# i2c_encoder_6.net
KiCad netlist of a schematic drawn in EAGLE
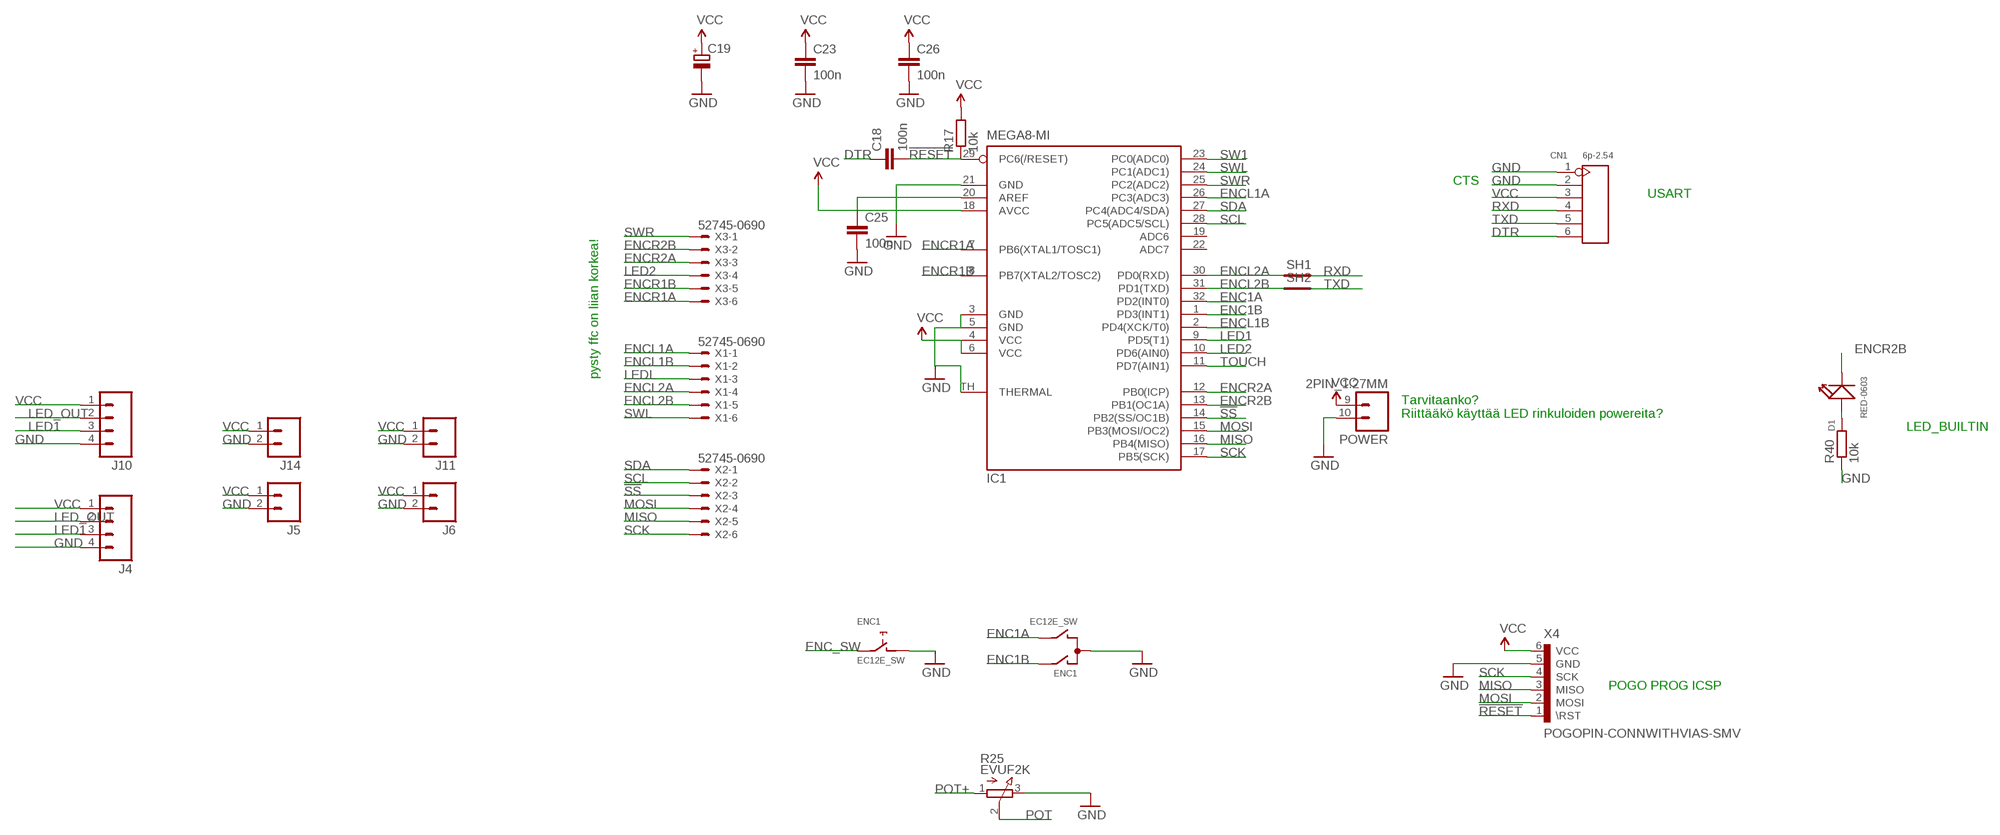
[diagram p0: schematic, sheet 1]
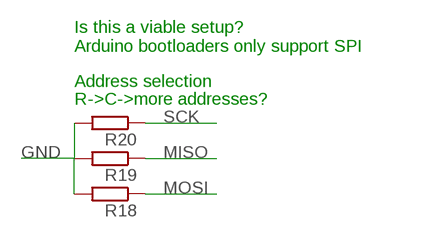
[diagram p1: schematic, sheet 2]
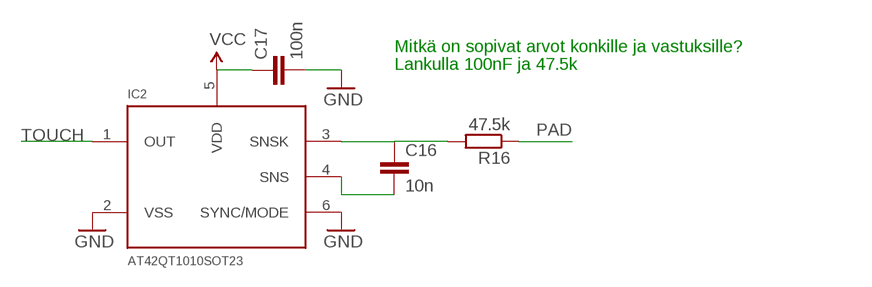
[diagram p2: schematic, sheet 3]
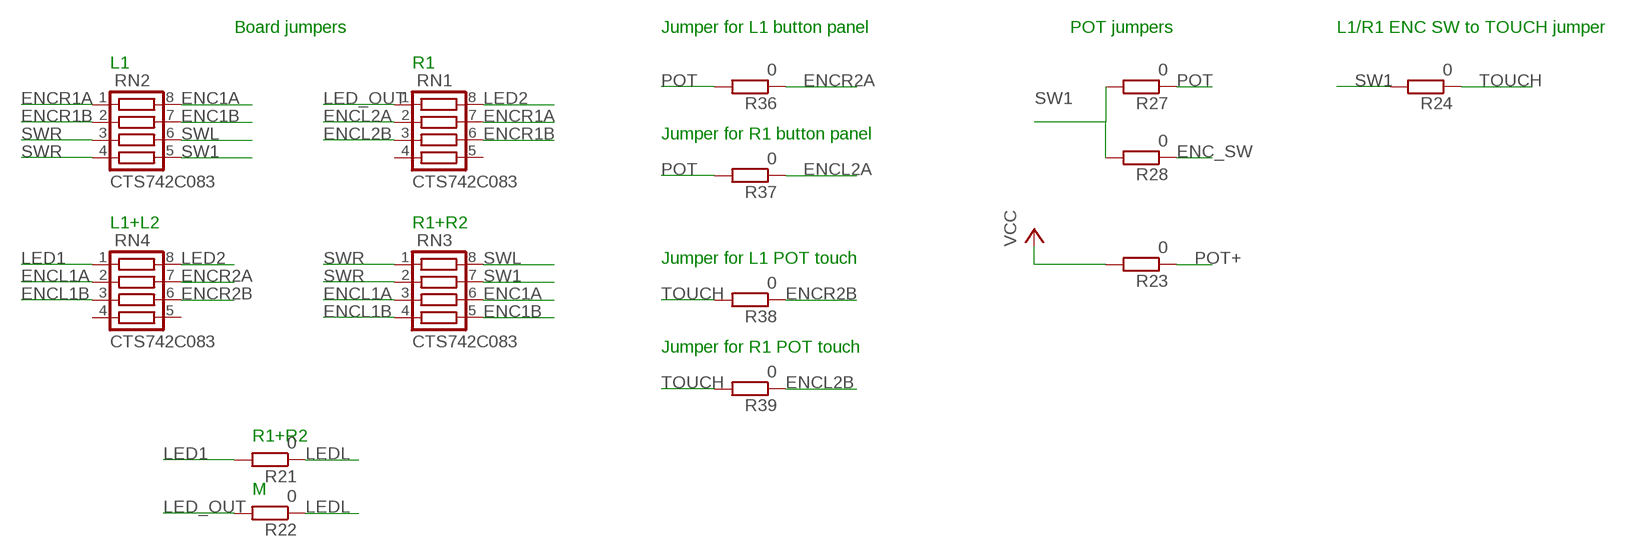
[diagram p3: schematic, sheet 4]
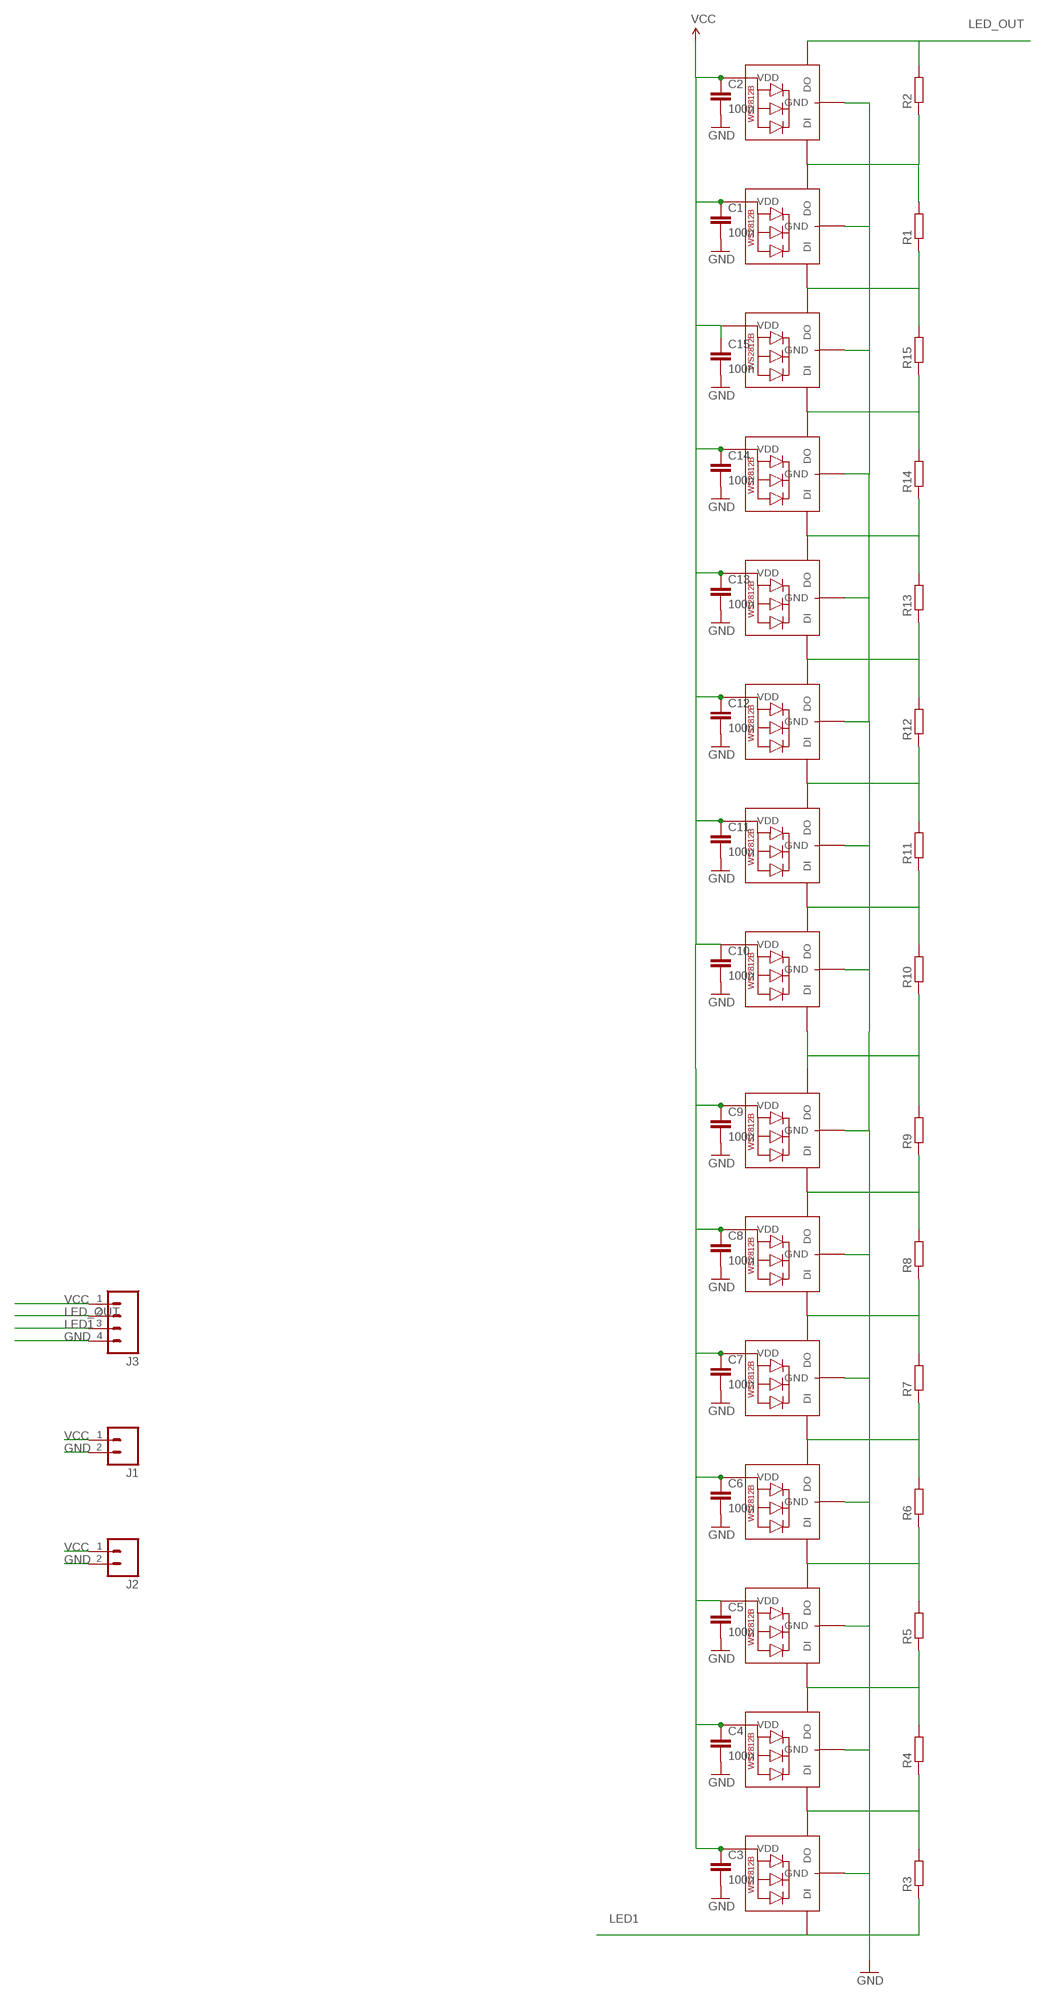
[diagram p4: schematic, sheet 5]
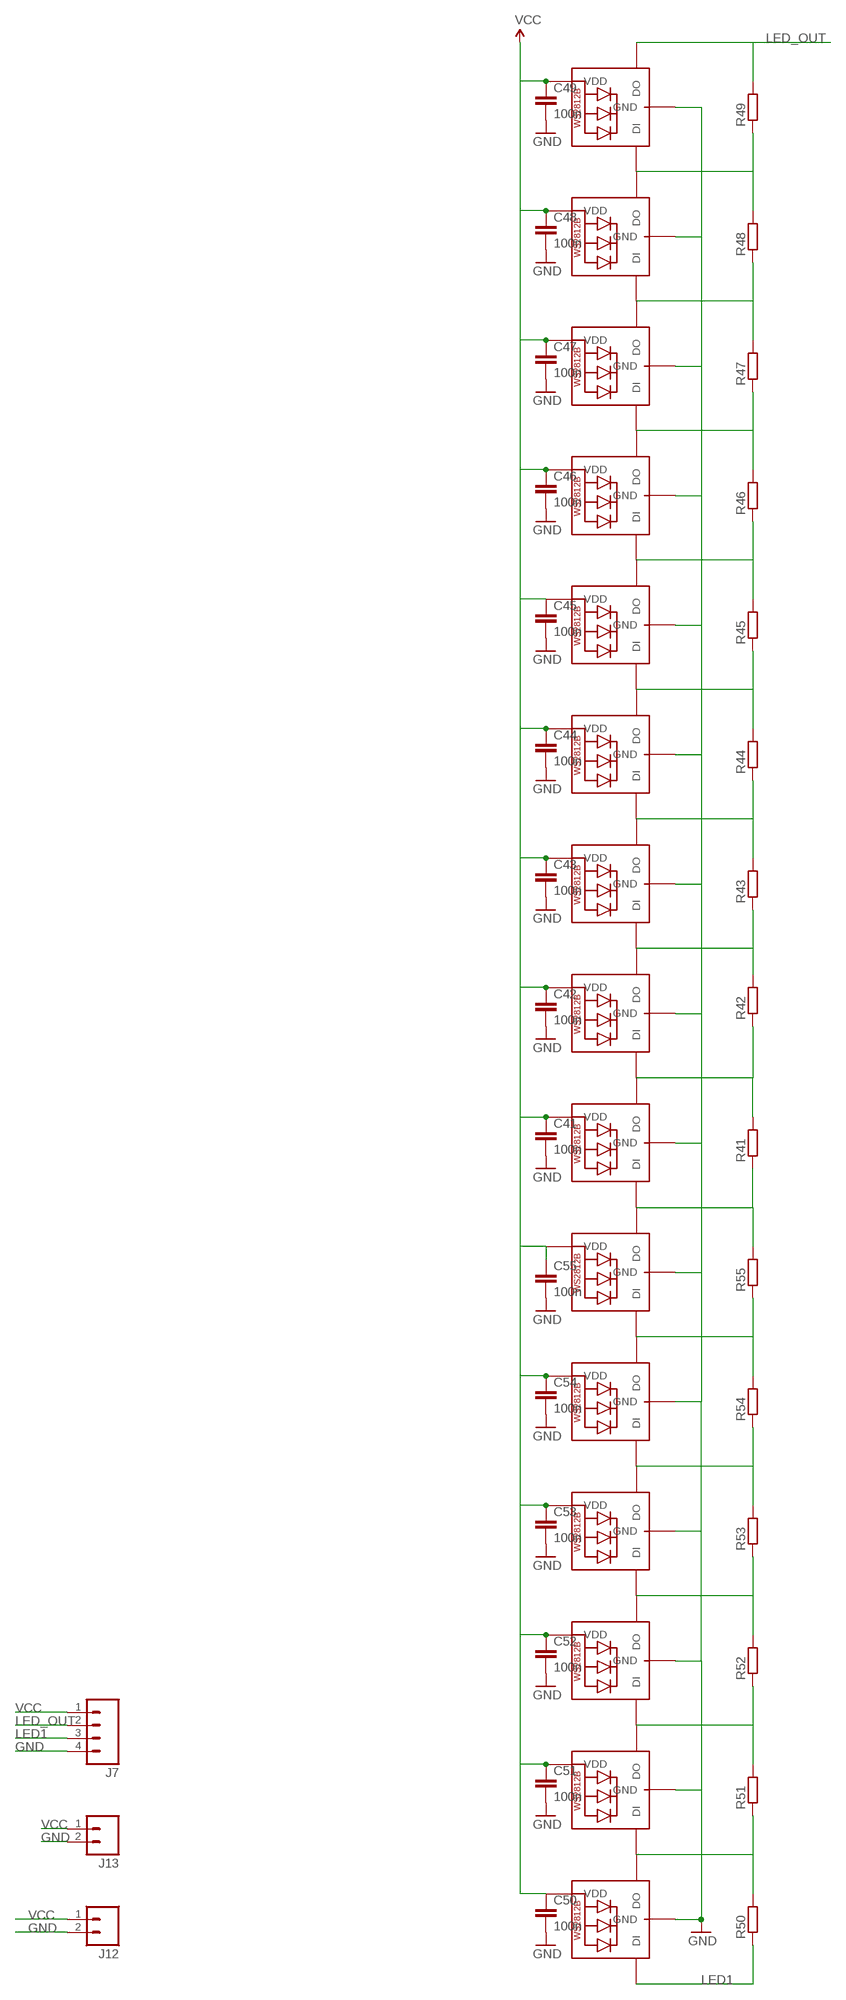
[diagram p5: schematic, sheet 6]
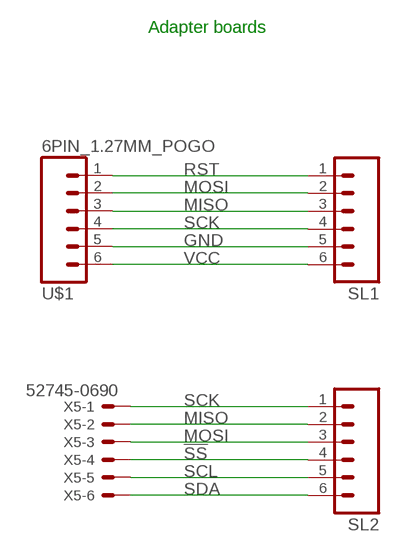
[diagram p6: schematic, sheet 7]
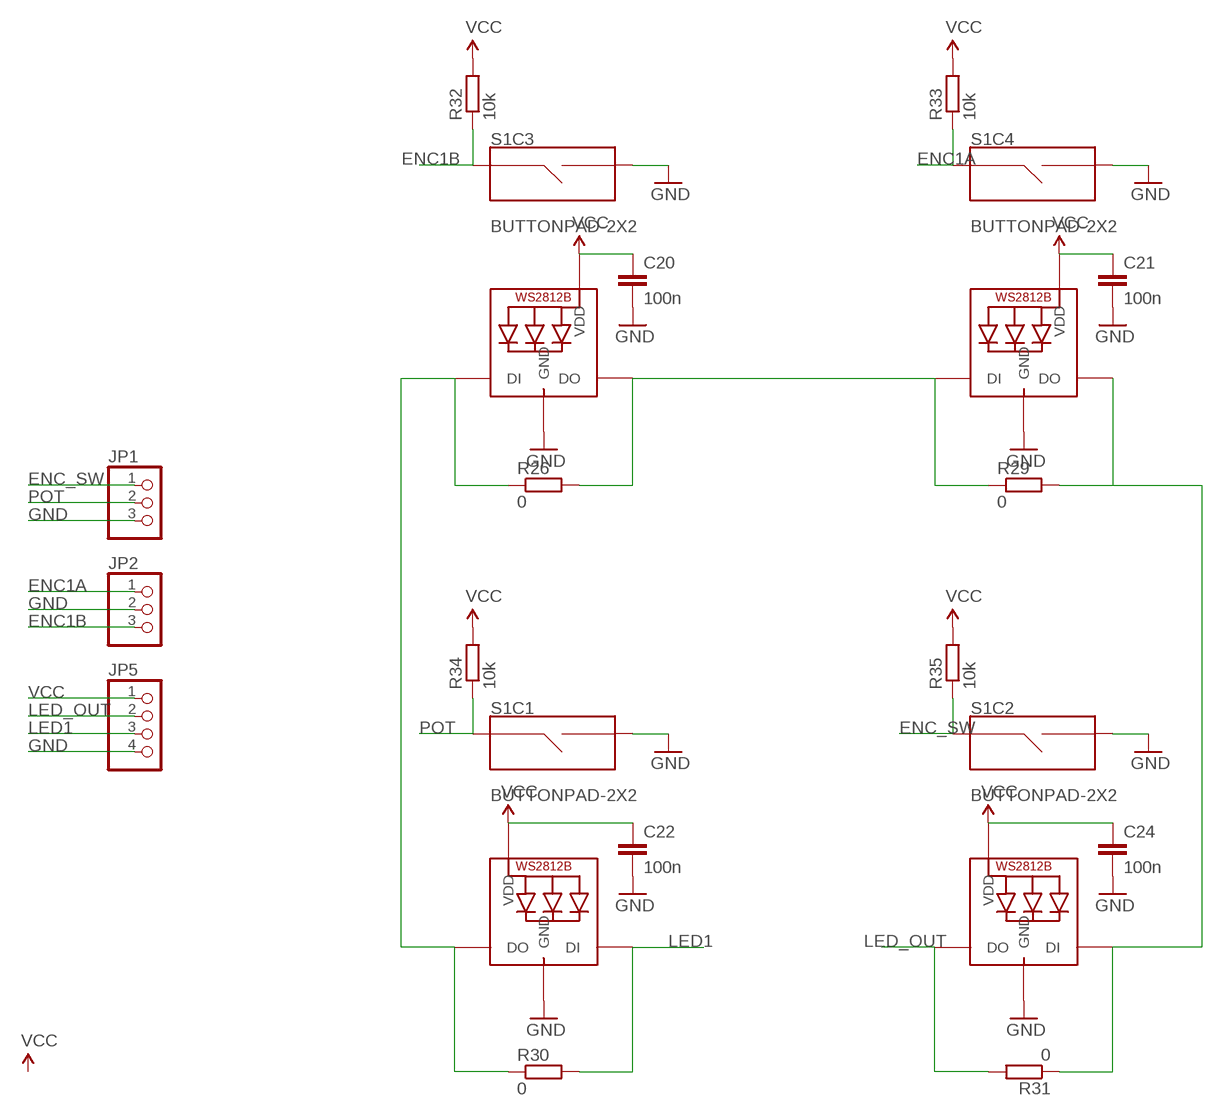
[diagram p7: schematic, sheet 8]

(export (version "E")
  (design (tool "Eeschema 10.0.6"))
  (components
    (comp (ref "C16")
      (value "10n")
      (footprint "eagle-import:0603-CAP")
      (libsource (lib "eagle-import") (part "CAP0603-CAP"))
    )
    (comp (ref "C17")
      (value "100n")
      (footprint "eagle-import:0603-CAP")
      (libsource (lib "eagle-import") (part "CAP0603-CAP"))
    )
    (comp (ref "IC2")
      (value "AT42QT1010SOT23")
      (footprint "eagle-import:SOT23-6")
      (libsource (lib "eagle-import") (part "AT42QT1010SOT23"))
    )
    (comp (ref "R16")
      (value "47.5k")
      (footprint "eagle-import:R0603")
      (libsource (lib "eagle-import") (part "R-EU_R0603"))
    )
    (comp (ref "SL1")
      (value "M06")
      (footprint "eagle-import:06P")
      (libsource (lib "eagle-import") (part "M06"))
    )
    (comp (ref "SL2")
      (value "M06")
      (footprint "eagle-import:06P")
      (libsource (lib "eagle-import") (part "M06"))
    )
    (comp (ref "U$1")
      (value "6PIN_1.27MM_POGO")
      (footprint "eagle-import:1X06-1.27MM_POGO")
      (libsource (lib "eagle-import") (part "6PIN_1.27MM_POGO"))
    )
    (comp (ref "X5")
      (value "52745-0690")
      (footprint "eagle-import:52745-0690")
      (fields (field (name "MF") "MOLEX"))
      (libsource (lib "eagle-import") (part "52745-0690"))
    )
    (comp (ref "R18")
      (value "R-EU_R0603")
      (footprint "eagle-import:R0603")
      (libsource (lib "eagle-import") (part "R-EU_R0603"))
    )
    (comp (ref "R19")
      (value "R-EU_R0603")
      (footprint "eagle-import:R0603")
      (libsource (lib "eagle-import") (part "R-EU_R0603"))
    )
    (comp (ref "R20")
      (value "R-EU_R0603")
      (footprint "eagle-import:R0603")
      (libsource (lib "eagle-import") (part "R-EU_R0603"))
    )
    (comp (ref "R21")
      (value "0")
      (footprint "eagle-import:R0603")
      (libsource (lib "eagle-import") (part "R-EU_R0603"))
    )
    (comp (ref "R22")
      (value "0")
      (footprint "eagle-import:R0603")
      (fields (field (name "SPICEPREFIX") "R"))
      (libsource (lib "eagle-import") (part "R-EU_R0603"))
    )
    (comp (ref "R23")
      (value "0")
      (footprint "eagle-import:R0603")
      (fields (field (name "SPICEPREFIX") "R"))
      (libsource (lib "eagle-import") (part "R-EU_R0603"))
    )
    (comp (ref "R24")
      (value "0")
      (footprint "eagle-import:R0603")
      (fields (field (name "SPICEPREFIX") "R"))
      (libsource (lib "eagle-import") (part "R-EU_R0603"))
    )
    (comp (ref "R27")
      (value "0")
      (footprint "eagle-import:R0603")
      (fields (field (name "SPICEPREFIX") "R"))
      (libsource (lib "eagle-import") (part "R-EU_R0603"))
    )
    (comp (ref "R28")
      (value "0")
      (footprint "eagle-import:R0603")
      (fields (field (name "SPICEPREFIX") "R"))
      (libsource (lib "eagle-import") (part "R-EU_R0603"))
    )
    (comp (ref "R36")
      (value "0")
      (footprint "eagle-import:R0603")
      (fields (field (name "SPICEPREFIX") "R"))
      (libsource (lib "eagle-import") (part "R-EU_R0603"))
    )
    (comp (ref "R37")
      (value "0")
      (footprint "eagle-import:R0603")
      (fields (field (name "SPICEPREFIX") "R"))
      (libsource (lib "eagle-import") (part "R-EU_R0603"))
    )
    (comp (ref "R38")
      (value "0")
      (footprint "eagle-import:R0603")
      (fields (field (name "SPICEPREFIX") "R"))
      (libsource (lib "eagle-import") (part "R-EU_R0603"))
    )
    (comp (ref "R39")
      (value "0")
      (footprint "eagle-import:R0603")
      (fields (field (name "SPICEPREFIX") "R"))
      (libsource (lib "eagle-import") (part "R-EU_R0603"))
    )
    (comp (ref "RN1")
      (value "CTS742C083")
      (footprint "eagle-import:CTS742C083")
      (libsource (lib "eagle-import") (part "CTS742C083"))
    )
    (comp (ref "RN2")
      (value "CTS742C083")
      (footprint "eagle-import:CTS742C083")
      (libsource (lib "eagle-import") (part "CTS742C083"))
    )
    (comp (ref "RN3")
      (value "CTS742C083")
      (footprint "eagle-import:CTS742C083")
      (libsource (lib "eagle-import") (part "CTS742C083"))
    )
    (comp (ref "RN4")
      (value "CTS742C083")
      (footprint "eagle-import:CTS742C083")
      (libsource (lib "eagle-import") (part "CTS742C083"))
    )
    (comp (ref "C18")
      (value "100n")
      (footprint "eagle-import:0603-CAP")
      (libsource (lib "eagle-import") (part "CAP0603-CAP"))
    )
    (comp (ref "C19")
      (value "CPOL-EUC")
      (footprint "eagle-import:PANASONIC_C")
      (libsource (lib "eagle-import") (part "CPOL-EUC"))
    )
    (comp (ref "C23")
      (value "100n")
      (footprint "eagle-import:0603-CAP")
      (libsource (lib "eagle-import") (part "CAP0603-CAP"))
    )
    (comp (ref "C25")
      (value "100n")
      (footprint "eagle-import:0603-CAP")
      (libsource (lib "eagle-import") (part "CAP0603-CAP"))
    )
    (comp (ref "C26")
      (value "100n")
      (footprint "eagle-import:0603-CAP")
      (libsource (lib "eagle-import") (part "CAP0603-CAP"))
    )
    (comp (ref "CN1")
      (value "6p-2.54")
      (footprint "eagle-import:H6-2.54")
      (fields (field (name "MPN") "F185-1106A1BSYC1"))
      (libsource (lib "eagle-import") (part "DIP-BLACK-FEMALE-HEADER-VERT(6P-2.54)"))
    )
    (comp (ref "D1")
      (value "RED-0603")
      (footprint "eagle-import:LED-0603")
      (fields (field (name "MPN") "19-217-R6C-AL1M2VY-3T"))
      (libsource (lib "eagle-import") (part "LED-SMD-RED-DIFFUSED(0603)"))
    )
    (comp (ref "ENC1")
      (value "EC12E_SW")
      (footprint "eagle-import:ALPS_EC12E_SW")
      (fields (field (name "MPN") "EC12E2424407"))
      (libsource (lib "eagle-import") (part "EC12E_SW"))
    )
    (comp (ref "IC1")
      (value "MEGA8-MI")
      (footprint "eagle-import:MLF32-TH")
      (fields (field (name "MPN") "ATMEGA88PA-MU"))
      (libsource (lib "eagle-import") (part "MEGA8-MI"))
    )
    (comp (ref "J4")
      (value "M04NO_SILK_ALL_ROUND")
      (footprint "eagle-import:1X04_NO_SILK_ALL_ROUND")
      (libsource (lib "eagle-import") (part "M04NO_SILK_ALL_ROUND"))
    )
    (comp (ref "J5")
      (value "M021X02_NO_SILK")
      (footprint "eagle-import:1X02_NO_SILK")
      (libsource (lib "eagle-import") (part "M021X02_NO_SILK"))
    )
    (comp (ref "J6")
      (value "M021X02_NO_SILK")
      (footprint "eagle-import:1X02_NO_SILK")
      (libsource (lib "eagle-import") (part "M021X02_NO_SILK"))
    )
    (comp (ref "J10")
      (value "M04NO_SILK_ALL_ROUND")
      (footprint "eagle-import:1X04_NO_SILK_ALL_ROUND")
      (libsource (lib "eagle-import") (part "M04NO_SILK_ALL_ROUND"))
    )
    (comp (ref "J11")
      (value "M021X02_NO_SILK")
      (footprint "eagle-import:1X02_NO_SILK")
      (libsource (lib "eagle-import") (part "M021X02_NO_SILK"))
    )
    (comp (ref "J14")
      (value "M021X02_NO_SILK")
      (footprint "eagle-import:1X02_NO_SILK")
      (libsource (lib "eagle-import") (part "M021X02_NO_SILK"))
    )
    (comp (ref "POWER")
      (value "2PIN_1.27MM")
      (footprint "eagle-import:1X02_1.27MM_NO_SILK")
      (libsource (lib "eagle-import") (part "2PIN_1.27MM"))
    )
    (comp (ref "R17")
      (value "10k")
      (footprint "eagle-import:R0603")
      (libsource (lib "eagle-import") (part "R-EU_R0603"))
    )
    (comp (ref "R25")
      (value "EVUF2K")
      (footprint "eagle-import:EVUFXK")
      (libsource (lib "eagle-import") (part "EVUF2K"))
    )
    (comp (ref "R40")
      (value "10k")
      (footprint "eagle-import:R0603")
      (libsource (lib "eagle-import") (part "R-EU_R0603"))
    )
    (comp (ref "SH1")
      (value "SHORT")
      (footprint "eagle-import:SHORT_TOP_8MIL")
      (libsource (lib "eagle-import") (part "SHORT"))
    )
    (comp (ref "SH2")
      (value "SHORT")
      (footprint "eagle-import:SHORT_TOP_8MIL")
      (libsource (lib "eagle-import") (part "SHORT"))
    )
    (comp (ref "X1")
      (value "52745-0690")
      (footprint "eagle-import:52745-0690")
      (fields (field (name "MF") "MOLEX"))
      (libsource (lib "eagle-import") (part "52745-0690"))
    )
    (comp (ref "X2")
      (value "52745-0690")
      (footprint "eagle-import:52745-0690")
      (fields (field (name "MF") "MOLEX"))
      (libsource (lib "eagle-import") (part "52745-0690"))
    )
    (comp (ref "X3")
      (value "52745-0690")
      (footprint "eagle-import:52745-0690")
      (fields (field (name "MF") "MOLEX"))
      (libsource (lib "eagle-import") (part "52745-0690"))
    )
    (comp (ref "X4")
      (value "POGOPIN-CONNWITHVIAS-SMV")
      (footprint "eagle-import:POGOPROG-CONN-OH-SMALLERVIAS")
      (libsource (lib "eagle-import") (part "POGOPIN-CONNWITHVIAS-SMV"))
    )
    (comp (ref "C20")
      (value "100n")
      (footprint "eagle-import:0603-CAP")
      (libsource (lib "eagle-import") (part "CAP0603-CAP"))
    )
    (comp (ref "C21")
      (value "100n")
      (footprint "eagle-import:0603-CAP")
      (libsource (lib "eagle-import") (part "CAP0603-CAP"))
    )
    (comp (ref "C22")
      (value "100n")
      (footprint "eagle-import:0603-CAP")
      (libsource (lib "eagle-import") (part "CAP0603-CAP"))
    )
    (comp (ref "C24")
      (value "100n")
      (footprint "eagle-import:0603-CAP")
      (libsource (lib "eagle-import") (part "CAP0603-CAP"))
    )
    (comp (ref "JP1")
      (value "PINHD-1X31X03_SMT")
      (footprint "eagle-import:1X03_SMT")
      (libsource (lib "eagle-import") (part "PINHD-1X31X03_SMT"))
    )
    (comp (ref "JP2")
      (value "PINHD-1X31X03_SMT")
      (footprint "eagle-import:1X03_SMT")
      (libsource (lib "eagle-import") (part "PINHD-1X31X03_SMT"))
    )
    (comp (ref "JP5")
      (value "PINHD-1X41X04_SMT")
      (footprint "eagle-import:1X04_SMT")
      (libsource (lib "eagle-import") (part "PINHD-1X41X04_SMT"))
    )
    (comp (ref "LED16")
      (value "WS2812B3535")
      (footprint "eagle-import:LED3535")
      (libsource (lib "eagle-import") (part "WS2812B3535"))
    )
    (comp (ref "LED17")
      (value "WS2812B3535")
      (footprint "eagle-import:LED3535")
      (libsource (lib "eagle-import") (part "WS2812B3535"))
    )
    (comp (ref "LED18")
      (value "WS2812B3535")
      (footprint "eagle-import:LED3535")
      (libsource (lib "eagle-import") (part "WS2812B3535"))
    )
    (comp (ref "LED19")
      (value "WS2812B3535")
      (footprint "eagle-import:LED3535")
      (libsource (lib "eagle-import") (part "WS2812B3535"))
    )
    (comp (ref "R26")
      (value "0")
      (footprint "eagle-import:R0603")
      (libsource (lib "eagle-import") (part "R-EU_R0603"))
    )
    (comp (ref "R29")
      (value "0")
      (footprint "eagle-import:R0603")
      (libsource (lib "eagle-import") (part "R-EU_R0603"))
    )
    (comp (ref "R30")
      (value "0")
      (footprint "eagle-import:R0603")
      (libsource (lib "eagle-import") (part "R-EU_R0603"))
    )
    (comp (ref "R31")
      (value "0")
      (footprint "eagle-import:R0603")
      (libsource (lib "eagle-import") (part "R-EU_R0603"))
    )
    (comp (ref "R32")
      (value "10k")
      (footprint "eagle-import:R0603")
      (libsource (lib "eagle-import") (part "R-EU_R0603"))
    )
    (comp (ref "R33")
      (value "10k")
      (footprint "eagle-import:R0603")
      (libsource (lib "eagle-import") (part "R-EU_R0603"))
    )
    (comp (ref "R34")
      (value "10k")
      (footprint "eagle-import:R0603")
      (libsource (lib "eagle-import") (part "R-EU_R0603"))
    )
    (comp (ref "R35")
      (value "10k")
      (footprint "eagle-import:R0603")
      (libsource (lib "eagle-import") (part "R-EU_R0603"))
    )
    (comp (ref "S1")
      (value "BUTTONPAD-2X2")
      (footprint "eagle-import:BUTTONPAD-2X2-SINGLE")
      (libsource (lib "eagle-import") (part "BUTTONPAD-2X2"))
    )
    (comp (ref "C1")
      (value "100n")
      (footprint "eagle-import:0603-CAP")
      (libsource (lib "eagle-import") (part "CAP0603-CAP"))
    )
    (comp (ref "C2")
      (value "100n")
      (footprint "eagle-import:0603-CAP")
      (libsource (lib "eagle-import") (part "CAP0603-CAP"))
    )
    (comp (ref "C3")
      (value "100n")
      (footprint "eagle-import:0603-CAP")
      (libsource (lib "eagle-import") (part "CAP0603-CAP"))
    )
    (comp (ref "C4")
      (value "100n")
      (footprint "eagle-import:0603-CAP")
      (libsource (lib "eagle-import") (part "CAP0603-CAP"))
    )
    (comp (ref "C5")
      (value "100n")
      (footprint "eagle-import:0603-CAP")
      (libsource (lib "eagle-import") (part "CAP0603-CAP"))
    )
    (comp (ref "C6")
      (value "100n")
      (footprint "eagle-import:0603-CAP")
      (libsource (lib "eagle-import") (part "CAP0603-CAP"))
    )
    (comp (ref "C7")
      (value "100n")
      (footprint "eagle-import:0603-CAP")
      (libsource (lib "eagle-import") (part "CAP0603-CAP"))
    )
    (comp (ref "C8")
      (value "100n")
      (footprint "eagle-import:0603-CAP")
      (libsource (lib "eagle-import") (part "CAP0603-CAP"))
    )
    (comp (ref "C9")
      (value "100n")
      (footprint "eagle-import:0603-CAP")
      (libsource (lib "eagle-import") (part "CAP0603-CAP"))
    )
    (comp (ref "C10")
      (value "100n")
      (footprint "eagle-import:0603-CAP")
      (libsource (lib "eagle-import") (part "CAP0603-CAP"))
    )
    (comp (ref "C11")
      (value "100n")
      (footprint "eagle-import:0603-CAP")
      (libsource (lib "eagle-import") (part "CAP0603-CAP"))
    )
    (comp (ref "C12")
      (value "100n")
      (footprint "eagle-import:0603-CAP")
      (libsource (lib "eagle-import") (part "CAP0603-CAP"))
    )
    (comp (ref "C13")
      (value "100n")
      (footprint "eagle-import:0603-CAP")
      (libsource (lib "eagle-import") (part "CAP0603-CAP"))
    )
    (comp (ref "C14")
      (value "100n")
      (footprint "eagle-import:0603-CAP")
      (libsource (lib "eagle-import") (part "CAP0603-CAP"))
    )
    (comp (ref "C15")
      (value "100n")
      (footprint "eagle-import:0603-CAP")
      (libsource (lib "eagle-import") (part "CAP0603-CAP"))
    )
    (comp (ref "J1")
      (value "M021X02_NO_SILK")
      (footprint "eagle-import:1X02_NO_SILK")
      (libsource (lib "eagle-import") (part "M021X02_NO_SILK"))
    )
    (comp (ref "J2")
      (value "M021X02_NO_SILK")
      (footprint "eagle-import:1X02_NO_SILK")
      (libsource (lib "eagle-import") (part "M021X02_NO_SILK"))
    )
    (comp (ref "J3")
      (value "M04NO_SILK_ALL_ROUND")
      (footprint "eagle-import:1X04_NO_SILK_ALL_ROUND")
      (libsource (lib "eagle-import") (part "M04NO_SILK_ALL_ROUND"))
    )
    (comp (ref "LED1")
      (value "WS2812B3535")
      (footprint "eagle-import:LED3535")
      (libsource (lib "eagle-import") (part "WS2812B3535"))
    )
    (comp (ref "LED2")
      (value "WS2812B3535")
      (footprint "eagle-import:LED3535")
      (libsource (lib "eagle-import") (part "WS2812B3535"))
    )
    (comp (ref "LED3")
      (value "WS2812B3535")
      (footprint "eagle-import:LED3535")
      (libsource (lib "eagle-import") (part "WS2812B3535"))
    )
    (comp (ref "LED4")
      (value "WS2812B3535")
      (footprint "eagle-import:LED3535")
      (fields (field (name "SPICEPREFIX") "E"))
      (libsource (lib "eagle-import") (part "WS2812B3535"))
    )
    (comp (ref "LED5")
      (value "WS2812B3535")
      (footprint "eagle-import:LED3535")
      (libsource (lib "eagle-import") (part "WS2812B3535"))
    )
    (comp (ref "LED6")
      (value "WS2812B3535")
      (footprint "eagle-import:LED3535")
      (libsource (lib "eagle-import") (part "WS2812B3535"))
    )
    (comp (ref "LED7")
      (value "WS2812B3535")
      (footprint "eagle-import:LED3535")
      (libsource (lib "eagle-import") (part "WS2812B3535"))
    )
    (comp (ref "LED8")
      (value "WS2812B3535")
      (footprint "eagle-import:LED3535")
      (libsource (lib "eagle-import") (part "WS2812B3535"))
    )
    (comp (ref "LED9")
      (value "WS2812B3535")
      (footprint "eagle-import:LED3535")
      (libsource (lib "eagle-import") (part "WS2812B3535"))
    )
    (comp (ref "LED10")
      (value "WS2812B3535")
      (footprint "eagle-import:LED3535")
      (libsource (lib "eagle-import") (part "WS2812B3535"))
    )
    (comp (ref "LED11")
      (value "WS2812B3535")
      (footprint "eagle-import:LED3535")
      (libsource (lib "eagle-import") (part "WS2812B3535"))
    )
    (comp (ref "LED12")
      (value "WS2812B3535")
      (footprint "eagle-import:LED3535")
      (libsource (lib "eagle-import") (part "WS2812B3535"))
    )
    (comp (ref "LED13")
      (value "WS2812B3535")
      (footprint "eagle-import:LED3535")
      (libsource (lib "eagle-import") (part "WS2812B3535"))
    )
    (comp (ref "LED14")
      (value "WS2812B3535")
      (footprint "eagle-import:LED3535")
      (libsource (lib "eagle-import") (part "WS2812B3535"))
    )
    (comp (ref "LED15")
      (value "WS2812B3535")
      (footprint "eagle-import:LED3535")
      (libsource (lib "eagle-import") (part "WS2812B3535"))
    )
    (comp (ref "R1")
      (value "R-EU_R0603")
      (footprint "eagle-import:R0603")
      (libsource (lib "eagle-import") (part "R-EU_R0603"))
    )
    (comp (ref "R2")
      (value "R-EU_R0603")
      (footprint "eagle-import:R0603")
      (libsource (lib "eagle-import") (part "R-EU_R0603"))
    )
    (comp (ref "R3")
      (value "R-EU_R0603")
      (footprint "eagle-import:R0603")
      (libsource (lib "eagle-import") (part "R-EU_R0603"))
    )
    (comp (ref "R4")
      (value "R-EU_R0603")
      (footprint "eagle-import:R0603")
      (libsource (lib "eagle-import") (part "R-EU_R0603"))
    )
    (comp (ref "R5")
      (value "R-EU_R0603")
      (footprint "eagle-import:R0603")
      (libsource (lib "eagle-import") (part "R-EU_R0603"))
    )
    (comp (ref "R6")
      (value "R-EU_R0603")
      (footprint "eagle-import:R0603")
      (libsource (lib "eagle-import") (part "R-EU_R0603"))
    )
    (comp (ref "R7")
      (value "R-EU_R0603")
      (footprint "eagle-import:R0603")
      (libsource (lib "eagle-import") (part "R-EU_R0603"))
    )
    (comp (ref "R8")
      (value "R-EU_R0603")
      (footprint "eagle-import:R0603")
      (libsource (lib "eagle-import") (part "R-EU_R0603"))
    )
    (comp (ref "R9")
      (value "R-EU_R0603")
      (footprint "eagle-import:R0603")
      (libsource (lib "eagle-import") (part "R-EU_R0603"))
    )
    (comp (ref "R10")
      (value "R-EU_R0603")
      (footprint "eagle-import:R0603")
      (libsource (lib "eagle-import") (part "R-EU_R0603"))
    )
    (comp (ref "R11")
      (value "R-EU_R0603")
      (footprint "eagle-import:R0603")
      (libsource (lib "eagle-import") (part "R-EU_R0603"))
    )
    (comp (ref "R12")
      (value "R-EU_R0603")
      (footprint "eagle-import:R0603")
      (libsource (lib "eagle-import") (part "R-EU_R0603"))
    )
    (comp (ref "R13")
      (value "R-EU_R0603")
      (footprint "eagle-import:R0603")
      (libsource (lib "eagle-import") (part "R-EU_R0603"))
    )
    (comp (ref "R14")
      (value "R-EU_R0603")
      (footprint "eagle-import:R0603")
      (libsource (lib "eagle-import") (part "R-EU_R0603"))
    )
    (comp (ref "R15")
      (value "R-EU_R0603")
      (footprint "eagle-import:R0603")
      (libsource (lib "eagle-import") (part "R-EU_R0603"))
    )
    (comp (ref "C41")
      (value "100n")
      (footprint "eagle-import:0603-CAP")
      (libsource (lib "eagle-import") (part "CAP0603-CAP"))
    )
    (comp (ref "C42")
      (value "100n")
      (footprint "eagle-import:0603-CAP")
      (libsource (lib "eagle-import") (part "CAP0603-CAP"))
    )
    (comp (ref "C43")
      (value "100n")
      (footprint "eagle-import:0603-CAP")
      (libsource (lib "eagle-import") (part "CAP0603-CAP"))
    )
    (comp (ref "C44")
      (value "100n")
      (footprint "eagle-import:0603-CAP")
      (libsource (lib "eagle-import") (part "CAP0603-CAP"))
    )
    (comp (ref "C45")
      (value "100n")
      (footprint "eagle-import:0603-CAP")
      (libsource (lib "eagle-import") (part "CAP0603-CAP"))
    )
    (comp (ref "C46")
      (value "100n")
      (footprint "eagle-import:0603-CAP")
      (libsource (lib "eagle-import") (part "CAP0603-CAP"))
    )
    (comp (ref "C47")
      (value "100n")
      (footprint "eagle-import:0603-CAP")
      (libsource (lib "eagle-import") (part "CAP0603-CAP"))
    )
    (comp (ref "C48")
      (value "100n")
      (footprint "eagle-import:0603-CAP")
      (libsource (lib "eagle-import") (part "CAP0603-CAP"))
    )
    (comp (ref "C49")
      (value "100n")
      (footprint "eagle-import:0603-CAP")
      (libsource (lib "eagle-import") (part "CAP0603-CAP"))
    )
    (comp (ref "C50")
      (value "100n")
      (footprint "eagle-import:0603-CAP")
      (libsource (lib "eagle-import") (part "CAP0603-CAP"))
    )
    (comp (ref "C51")
      (value "100n")
      (footprint "eagle-import:0603-CAP")
      (libsource (lib "eagle-import") (part "CAP0603-CAP"))
    )
    (comp (ref "C52")
      (value "100n")
      (footprint "eagle-import:0603-CAP")
      (libsource (lib "eagle-import") (part "CAP0603-CAP"))
    )
    (comp (ref "C53")
      (value "100n")
      (footprint "eagle-import:0603-CAP")
      (libsource (lib "eagle-import") (part "CAP0603-CAP"))
    )
    (comp (ref "C54")
      (value "100n")
      (footprint "eagle-import:0603-CAP")
      (libsource (lib "eagle-import") (part "CAP0603-CAP"))
    )
    (comp (ref "C55")
      (value "100n")
      (footprint "eagle-import:0603-CAP")
      (libsource (lib "eagle-import") (part "CAP0603-CAP"))
    )
    (comp (ref "J7")
      (value "M04NO_SILK_ALL_ROUND")
      (footprint "eagle-import:1X04_NO_SILK_ALL_ROUND")
      (libsource (lib "eagle-import") (part "M04NO_SILK_ALL_ROUND"))
    )
    (comp (ref "J12")
      (value "M021X02_NO_SILK")
      (footprint "eagle-import:1X02_NO_SILK")
      (libsource (lib "eagle-import") (part "M021X02_NO_SILK"))
    )
    (comp (ref "J13")
      (value "M021X02_NO_SILK")
      (footprint "eagle-import:1X02_NO_SILK")
      (libsource (lib "eagle-import") (part "M021X02_NO_SILK"))
    )
    (comp (ref "LED31")
      (value "WS2812B3535")
      (footprint "eagle-import:LED3535")
      (libsource (lib "eagle-import") (part "WS2812B3535"))
    )
    (comp (ref "LED32")
      (value "WS2812B3535")
      (footprint "eagle-import:LED3535")
      (libsource (lib "eagle-import") (part "WS2812B3535"))
    )
    (comp (ref "LED33")
      (value "WS2812B3535")
      (footprint "eagle-import:LED3535")
      (libsource (lib "eagle-import") (part "WS2812B3535"))
    )
    (comp (ref "LED34")
      (value "WS2812B3535")
      (footprint "eagle-import:LED3535")
      (libsource (lib "eagle-import") (part "WS2812B3535"))
    )
    (comp (ref "LED35")
      (value "WS2812B3535")
      (footprint "eagle-import:LED3535")
      (libsource (lib "eagle-import") (part "WS2812B3535"))
    )
    (comp (ref "LED36")
      (value "WS2812B3535")
      (footprint "eagle-import:LED3535")
      (libsource (lib "eagle-import") (part "WS2812B3535"))
    )
    (comp (ref "LED37")
      (value "WS2812B3535")
      (footprint "eagle-import:LED3535")
      (libsource (lib "eagle-import") (part "WS2812B3535"))
    )
    (comp (ref "LED38")
      (value "WS2812B3535")
      (footprint "eagle-import:LED3535")
      (libsource (lib "eagle-import") (part "WS2812B3535"))
    )
    (comp (ref "LED39")
      (value "WS2812B3535")
      (footprint "eagle-import:LED3535")
      (libsource (lib "eagle-import") (part "WS2812B3535"))
    )
    (comp (ref "LED40")
      (value "WS2812B3535")
      (footprint "eagle-import:LED3535")
      (libsource (lib "eagle-import") (part "WS2812B3535"))
    )
    (comp (ref "LED41")
      (value "WS2812B3535")
      (footprint "eagle-import:LED3535")
      (libsource (lib "eagle-import") (part "WS2812B3535"))
    )
    (comp (ref "LED42")
      (value "WS2812B3535")
      (footprint "eagle-import:LED3535")
      (libsource (lib "eagle-import") (part "WS2812B3535"))
    )
    (comp (ref "LED43")
      (value "WS2812B3535")
      (footprint "eagle-import:LED3535")
      (libsource (lib "eagle-import") (part "WS2812B3535"))
    )
    (comp (ref "LED44")
      (value "WS2812B3535")
      (footprint "eagle-import:LED3535")
      (libsource (lib "eagle-import") (part "WS2812B3535"))
    )
    (comp (ref "LED45")
      (value "WS2812B3535")
      (footprint "eagle-import:LED3535")
      (libsource (lib "eagle-import") (part "WS2812B3535"))
    )
    (comp (ref "R41")
      (value "R-EU_R0603")
      (footprint "eagle-import:R0603")
      (libsource (lib "eagle-import") (part "R-EU_R0603"))
    )
    (comp (ref "R42")
      (value "R-EU_R0603")
      (footprint "eagle-import:R0603")
      (libsource (lib "eagle-import") (part "R-EU_R0603"))
    )
    (comp (ref "R43")
      (value "R-EU_R0603")
      (footprint "eagle-import:R0603")
      (libsource (lib "eagle-import") (part "R-EU_R0603"))
    )
    (comp (ref "R44")
      (value "R-EU_R0603")
      (footprint "eagle-import:R0603")
      (libsource (lib "eagle-import") (part "R-EU_R0603"))
    )
    (comp (ref "R45")
      (value "R-EU_R0603")
      (footprint "eagle-import:R0603")
      (libsource (lib "eagle-import") (part "R-EU_R0603"))
    )
    (comp (ref "R46")
      (value "R-EU_R0603")
      (footprint "eagle-import:R0603")
      (libsource (lib "eagle-import") (part "R-EU_R0603"))
    )
    (comp (ref "R47")
      (value "R-EU_R0603")
      (footprint "eagle-import:R0603")
      (libsource (lib "eagle-import") (part "R-EU_R0603"))
    )
    (comp (ref "R48")
      (value "R-EU_R0603")
      (footprint "eagle-import:R0603")
      (libsource (lib "eagle-import") (part "R-EU_R0603"))
    )
    (comp (ref "R49")
      (value "R-EU_R0603")
      (footprint "eagle-import:R0603")
      (libsource (lib "eagle-import") (part "R-EU_R0603"))
    )
    (comp (ref "R50")
      (value "R-EU_R0603")
      (footprint "eagle-import:R0603")
      (libsource (lib "eagle-import") (part "R-EU_R0603"))
    )
    (comp (ref "R51")
      (value "R-EU_R0603")
      (footprint "eagle-import:R0603")
      (libsource (lib "eagle-import") (part "R-EU_R0603"))
    )
    (comp (ref "R52")
      (value "R-EU_R0603")
      (footprint "eagle-import:R0603")
      (libsource (lib "eagle-import") (part "R-EU_R0603"))
    )
    (comp (ref "R53")
      (value "R-EU_R0603")
      (footprint "eagle-import:R0603")
      (libsource (lib "eagle-import") (part "R-EU_R0603"))
    )
    (comp (ref "R54")
      (value "R-EU_R0603")
      (footprint "eagle-import:R0603")
      (libsource (lib "eagle-import") (part "R-EU_R0603"))
    )
    (comp (ref "R55")
      (value "R-EU_R0603")
      (footprint "eagle-import:R0603")
      (libsource (lib "eagle-import") (part "R-EU_R0603"))
    )
  )
  (nets
    (net (code "1") (name "DTR") (class "Default")
      (node (ref "C18") (pin "1") (pinfunction "1_1") (pintype "passive"))
      (node (ref "CN1") (pin "6") (pinfunction "6_6") (pintype "bidirectional"))
    )
    (net (code "2") (name "ENC1A") (class "Default")
      (node (ref "ENC1") (pin "B") (pinfunction "B_B") (pintype "passive"))
      (node (ref "IC1") (pin "32") (pinfunction "PD2(INT0)_32") (pintype "bidirectional"))
      (node (ref "JP2") (pin "1") (pinfunction "1_1") (pintype "passive"))
      (node (ref "R33") (pin "1") (pinfunction "1_1") (pintype "passive"))
      (node (ref "RN2") (pin "8") (pinfunction "8_8") (pintype "passive"))
      (node (ref "RN3") (pin "6") (pinfunction "6_6") (pintype "passive"))
      (node (ref "S1") (pin "SIG7") (pinfunction "SIG1_SIG7") (pintype "bidirectional"))
    )
    (net (code "3") (name "ENC1B") (class "Default")
      (node (ref "ENC1") (pin "A") (pinfunction "A_A") (pintype "passive"))
      (node (ref "IC1") (pin "1") (pinfunction "PD3(INT1)_1") (pintype "bidirectional"))
      (node (ref "JP2") (pin "3") (pinfunction "3_3") (pintype "passive"))
      (node (ref "R32") (pin "1") (pinfunction "1_1") (pintype "passive"))
      (node (ref "RN2") (pin "7") (pinfunction "7_7") (pintype "passive"))
      (node (ref "RN3") (pin "5") (pinfunction "5_5") (pintype "passive"))
      (node (ref "S1") (pin "SIG5") (pinfunction "SIG1_SIG5") (pintype "bidirectional"))
    )
    (net (code "4") (name "ENCL1A") (class "Default")
      (node (ref "IC1") (pin "26") (pinfunction "PC3(ADC3)_26") (pintype "bidirectional"))
      (node (ref "RN3") (pin "3") (pinfunction "3_3") (pintype "passive"))
      (node (ref "RN4") (pin "2") (pinfunction "2_2") (pintype "passive"))
      (node (ref "X1") (pin "1") (pinfunction "S_1") (pintype "passive"))
    )
    (net (code "5") (name "ENCL1B") (class "Default")
      (node (ref "IC1") (pin "2") (pinfunction "PD4(XCK/T0)_2") (pintype "bidirectional"))
      (node (ref "RN3") (pin "4") (pinfunction "4_4") (pintype "passive"))
      (node (ref "RN4") (pin "3") (pinfunction "3_3") (pintype "passive"))
      (node (ref "X1") (pin "2") (pinfunction "S_2") (pintype "passive"))
    )
    (net (code "6") (name "ENCL2A") (class "Default")
      (node (ref "IC1") (pin "30") (pinfunction "PD0(RXD)_30") (pintype "bidirectional"))
      (node (ref "R37") (pin "1") (pinfunction "1_1") (pintype "passive"))
      (node (ref "RN1") (pin "2") (pinfunction "2_2") (pintype "passive"))
      (node (ref "SH1") (pin "P$1") (pinfunction "P$1_P$1") (pintype "bidirectional"))
      (node (ref "X1") (pin "4") (pinfunction "S_4") (pintype "passive"))
    )
    (net (code "7") (name "ENCL2B") (class "Default")
      (node (ref "IC1") (pin "31") (pinfunction "PD1(TXD)_31") (pintype "bidirectional"))
      (node (ref "R39") (pin "1") (pinfunction "1_1") (pintype "passive"))
      (node (ref "RN1") (pin "3") (pinfunction "3_3") (pintype "passive"))
      (node (ref "SH2") (pin "P$1") (pinfunction "P$1_P$1") (pintype "bidirectional"))
      (node (ref "X1") (pin "5") (pinfunction "S_5") (pintype "passive"))
    )
    (net (code "8") (name "ENCR1A") (class "Default")
      (node (ref "IC1") (pin "7") (pinfunction "PB6(XTAL1/TOSC1)_7") (pintype "bidirectional"))
      (node (ref "RN1") (pin "7") (pinfunction "7_7") (pintype "passive"))
      (node (ref "RN2") (pin "1") (pinfunction "1_1") (pintype "passive"))
      (node (ref "X3") (pin "6") (pinfunction "S_6") (pintype "passive"))
    )
    (net (code "9") (name "ENCR1B") (class "Default")
      (node (ref "IC1") (pin "8") (pinfunction "PB7(XTAL2/TOSC2)_8") (pintype "bidirectional"))
      (node (ref "RN1") (pin "6") (pinfunction "6_6") (pintype "passive"))
      (node (ref "RN2") (pin "2") (pinfunction "2_2") (pintype "passive"))
      (node (ref "X3") (pin "5") (pinfunction "S_5") (pintype "passive"))
    )
    (net (code "10") (name "ENCR2A") (class "Default")
      (node (ref "IC1") (pin "12") (pinfunction "PB0(ICP)_12") (pintype "bidirectional"))
      (node (ref "R36") (pin "1") (pinfunction "1_1") (pintype "passive"))
      (node (ref "RN4") (pin "7") (pinfunction "7_7") (pintype "passive"))
      (node (ref "X3") (pin "3") (pinfunction "S_3") (pintype "passive"))
    )
    (net (code "11") (name "ENCR2B") (class "Default")
      (node (ref "D1") (pin "-") (pinfunction "-_-") (pintype "passive"))
      (node (ref "IC1") (pin "13") (pinfunction "PB1(OC1A)_13") (pintype "bidirectional"))
      (node (ref "R38") (pin "1") (pinfunction "1_1") (pintype "passive"))
      (node (ref "RN4") (pin "6") (pinfunction "6_6") (pintype "passive"))
      (node (ref "X3") (pin "2") (pinfunction "S_2") (pintype "passive"))
    )
    (net (code "12") (name "ENC_SW") (class "Default")
      (node (ref "ENC1") (pin "E") (pinfunction "2_E") (pintype "passive"))
      (node (ref "JP1") (pin "1") (pinfunction "1_1") (pintype "passive"))
      (node (ref "R28") (pin "1") (pinfunction "1_1") (pintype "passive"))
      (node (ref "R35") (pin "1") (pinfunction "1_1") (pintype "passive"))
      (node (ref "S1") (pin "SIG3") (pinfunction "SIG1_SIG3") (pintype "bidirectional"))
    )
    (net (code "13") (name "GND") (class "Default")
      (node (ref "C1") (pin "2") (pinfunction "2_2") (pintype "passive"))
      (node (ref "C10") (pin "2") (pinfunction "2_2") (pintype "passive"))
      (node (ref "C11") (pin "2") (pinfunction "2_2") (pintype "passive"))
      (node (ref "C12") (pin "2") (pinfunction "2_2") (pintype "passive"))
      (node (ref "C13") (pin "2") (pinfunction "2_2") (pintype "passive"))
      (node (ref "C14") (pin "2") (pinfunction "2_2") (pintype "passive"))
      (node (ref "C15") (pin "2") (pinfunction "2_2") (pintype "passive"))
      (node (ref "C17") (pin "2") (pinfunction "2_2") (pintype "passive"))
      (node (ref "C19") (pin "-") (pinfunction "-_-") (pintype "passive"))
      (node (ref "C2") (pin "2") (pinfunction "2_2") (pintype "passive"))
      (node (ref "C20") (pin "2") (pinfunction "2_2") (pintype "passive"))
      (node (ref "C21") (pin "2") (pinfunction "2_2") (pintype "passive"))
      (node (ref "C22") (pin "2") (pinfunction "2_2") (pintype "passive"))
      (node (ref "C23") (pin "2") (pinfunction "2_2") (pintype "passive"))
      (node (ref "C24") (pin "2") (pinfunction "2_2") (pintype "passive"))
      (node (ref "C25") (pin "2") (pinfunction "2_2") (pintype "passive"))
      (node (ref "C26") (pin "2") (pinfunction "2_2") (pintype "passive"))
      (node (ref "C3") (pin "2") (pinfunction "2_2") (pintype "passive"))
      (node (ref "C4") (pin "2") (pinfunction "2_2") (pintype "passive"))
      (node (ref "C41") (pin "2") (pinfunction "2_2") (pintype "passive"))
      (node (ref "C42") (pin "2") (pinfunction "2_2") (pintype "passive"))
      (node (ref "C43") (pin "2") (pinfunction "2_2") (pintype "passive"))
      (node (ref "C44") (pin "2") (pinfunction "2_2") (pintype "passive"))
      (node (ref "C45") (pin "2") (pinfunction "2_2") (pintype "passive"))
      (node (ref "C46") (pin "2") (pinfunction "2_2") (pintype "passive"))
      (node (ref "C47") (pin "2") (pinfunction "2_2") (pintype "passive"))
      (node (ref "C48") (pin "2") (pinfunction "2_2") (pintype "passive"))
      (node (ref "C49") (pin "2") (pinfunction "2_2") (pintype "passive"))
      (node (ref "C5") (pin "2") (pinfunction "2_2") (pintype "passive"))
      (node (ref "C50") (pin "2") (pinfunction "2_2") (pintype "passive"))
      (node (ref "C51") (pin "2") (pinfunction "2_2") (pintype "passive"))
      (node (ref "C52") (pin "2") (pinfunction "2_2") (pintype "passive"))
      (node (ref "C53") (pin "2") (pinfunction "2_2") (pintype "passive"))
      (node (ref "C54") (pin "2") (pinfunction "2_2") (pintype "passive"))
      (node (ref "C55") (pin "2") (pinfunction "2_2") (pintype "passive"))
      (node (ref "C6") (pin "2") (pinfunction "2_2") (pintype "passive"))
      (node (ref "C7") (pin "2") (pinfunction "2_2") (pintype "passive"))
      (node (ref "C8") (pin "2") (pinfunction "2_2") (pintype "passive"))
      (node (ref "C9") (pin "2") (pinfunction "2_2") (pintype "passive"))
      (node (ref "CN1") (pin "1") (pinfunction "1_1") (pintype "bidirectional"))
      (node (ref "CN1") (pin "2") (pinfunction "2_2") (pintype "bidirectional"))
      (node (ref "ENC1") (pin "C") (pinfunction "C_C") (pintype "passive"))
      (node (ref "ENC1") (pin "D") (pinfunction "1_D") (pintype "passive"))
      (node (ref "IC1") (pin "21") (pinfunction "GND_21") (pintype "power_in"))
      (node (ref "IC1") (pin "3") (pinfunction "GND_3") (pintype "power_in"))
      (node (ref "IC1") (pin "5") (pinfunction "GND_5") (pintype "power_in"))
      (node (ref "IC1") (pin "TH") (pinfunction "THERMAL_TH") (pintype "passive"))
      (node (ref "IC2") (pin "2") (pinfunction "VSS_2") (pintype "bidirectional"))
      (node (ref "IC2") (pin "6") (pinfunction "SYNC/MODE_6") (pintype "bidirectional"))
      (node (ref "J1") (pin "2") (pinfunction "2_2") (pintype "passive"))
      (node (ref "J10") (pin "4") (pinfunction "4_4") (pintype "passive"))
      (node (ref "J11") (pin "2") (pinfunction "2_2") (pintype "passive"))
      (node (ref "J12") (pin "2") (pinfunction "2_2") (pintype "passive"))
      (node (ref "J13") (pin "2") (pinfunction "2_2") (pintype "passive"))
      (node (ref "J14") (pin "2") (pinfunction "2_2") (pintype "passive"))
      (node (ref "J2") (pin "2") (pinfunction "2_2") (pintype "passive"))
      (node (ref "J3") (pin "4") (pinfunction "4_4") (pintype "passive"))
      (node (ref "J4") (pin "4") (pinfunction "4_4") (pintype "passive"))
      (node (ref "J5") (pin "2") (pinfunction "2_2") (pintype "passive"))
      (node (ref "J6") (pin "2") (pinfunction "2_2") (pintype "passive"))
      (node (ref "J7") (pin "4") (pinfunction "4_4") (pintype "passive"))
      (node (ref "JP1") (pin "3") (pinfunction "3_3") (pintype "passive"))
      (node (ref "JP2") (pin "2") (pinfunction "2_2") (pintype "passive"))
      (node (ref "JP5") (pin "4") (pinfunction "4_4") (pintype "passive"))
      (node (ref "LED1") (pin "4") (pinfunction "GND_4") (pintype "power_in"))
      (node (ref "LED10") (pin "4") (pinfunction "GND_4") (pintype "power_in"))
      (node (ref "LED11") (pin "4") (pinfunction "GND_4") (pintype "power_in"))
      (node (ref "LED12") (pin "4") (pinfunction "GND_4") (pintype "power_in"))
      (node (ref "LED13") (pin "4") (pinfunction "GND_4") (pintype "power_in"))
      (node (ref "LED14") (pin "4") (pinfunction "GND_4") (pintype "power_in"))
      (node (ref "LED15") (pin "4") (pinfunction "GND_4") (pintype "power_in"))
      (node (ref "LED16") (pin "4") (pinfunction "GND_4") (pintype "power_in"))
      (node (ref "LED17") (pin "4") (pinfunction "GND_4") (pintype "power_in"))
      (node (ref "LED18") (pin "4") (pinfunction "GND_4") (pintype "power_in"))
      (node (ref "LED19") (pin "4") (pinfunction "GND_4") (pintype "power_in"))
      (node (ref "LED2") (pin "4") (pinfunction "GND_4") (pintype "power_in"))
      (node (ref "LED3") (pin "4") (pinfunction "GND_4") (pintype "power_in"))
      (node (ref "LED31") (pin "4") (pinfunction "GND_4") (pintype "power_in"))
      (node (ref "LED32") (pin "4") (pinfunction "GND_4") (pintype "power_in"))
      (node (ref "LED33") (pin "4") (pinfunction "GND_4") (pintype "power_in"))
      (node (ref "LED34") (pin "4") (pinfunction "GND_4") (pintype "power_in"))
      (node (ref "LED35") (pin "4") (pinfunction "GND_4") (pintype "power_in"))
      (node (ref "LED36") (pin "4") (pinfunction "GND_4") (pintype "power_in"))
      (node (ref "LED37") (pin "4") (pinfunction "GND_4") (pintype "power_in"))
      (node (ref "LED38") (pin "4") (pinfunction "GND_4") (pintype "power_in"))
      (node (ref "LED39") (pin "4") (pinfunction "GND_4") (pintype "power_in"))
      (node (ref "LED4") (pin "4") (pinfunction "GND_4") (pintype "power_in"))
      (node (ref "LED40") (pin "4") (pinfunction "GND_4") (pintype "power_in"))
      (node (ref "LED41") (pin "4") (pinfunction "GND_4") (pintype "power_in"))
      (node (ref "LED42") (pin "4") (pinfunction "GND_4") (pintype "power_in"))
      (node (ref "LED43") (pin "4") (pinfunction "GND_4") (pintype "power_in"))
      (node (ref "LED44") (pin "4") (pinfunction "GND_4") (pintype "power_in"))
      (node (ref "LED45") (pin "4") (pinfunction "GND_4") (pintype "power_in"))
      (node (ref "LED5") (pin "4") (pinfunction "GND_4") (pintype "power_in"))
      (node (ref "LED6") (pin "4") (pinfunction "GND_4") (pintype "power_in"))
      (node (ref "LED7") (pin "4") (pinfunction "GND_4") (pintype "power_in"))
      (node (ref "LED8") (pin "4") (pinfunction "GND_4") (pintype "power_in"))
      (node (ref "LED9") (pin "4") (pinfunction "GND_4") (pintype "power_in"))
      (node (ref "POWER") (pin "10") (pinfunction "2_10") (pintype "passive"))
      (node (ref "R18") (pin "2") (pinfunction "2_2") (pintype "passive"))
      (node (ref "R19") (pin "2") (pinfunction "2_2") (pintype "passive"))
      (node (ref "R20") (pin "2") (pinfunction "2_2") (pintype "passive"))
      (node (ref "R25") (pin "3") (pinfunction "E_3") (pintype "passive"))
      (node (ref "R40") (pin "1") (pinfunction "1_1") (pintype "passive"))
      (node (ref "S1") (pin "SIG2") (pinfunction "SIG2_SIG2") (pintype "bidirectional"))
      (node (ref "S1") (pin "SIG4") (pinfunction "SIG2_SIG4") (pintype "bidirectional"))
      (node (ref "S1") (pin "SIG6") (pinfunction "SIG2_SIG6") (pintype "bidirectional"))
      (node (ref "S1") (pin "SIG8") (pinfunction "SIG2_SIG8") (pintype "bidirectional"))
      (node (ref "SL1") (pin "5") (pinfunction "5_5") (pintype "passive"))
      (node (ref "U$1") (pin "5") (pinfunction "5_5") (pintype "passive"))
      (node (ref "X4") (pin "5") (pinfunction "GND_5") (pintype "bidirectional"))
    )
    (net (code "14") (name "LED1") (class "Default")
      (node (ref "IC1") (pin "9") (pinfunction "PD5(T1)_9") (pintype "bidirectional"))
      (node (ref "J10") (pin "3") (pinfunction "3_3") (pintype "passive"))
      (node (ref "J3") (pin "3") (pinfunction "3_3") (pintype "passive"))
      (node (ref "J4") (pin "3") (pinfunction "3_3") (pintype "passive"))
      (node (ref "J7") (pin "3") (pinfunction "3_3") (pintype "passive"))
      (node (ref "JP5") (pin "3") (pinfunction "3_3") (pintype "passive"))
      (node (ref "LED1") (pin "1") (pinfunction "DI_1") (pintype "input"))
      (node (ref "LED16") (pin "1") (pinfunction "DI_1") (pintype "input"))
      (node (ref "LED31") (pin "1") (pinfunction "DI_1") (pintype "input"))
      (node (ref "R21") (pin "2") (pinfunction "2_2") (pintype "passive"))
      (node (ref "R3") (pin "1") (pinfunction "1_1") (pintype "passive"))
      (node (ref "R30") (pin "2") (pinfunction "2_2") (pintype "passive"))
      (node (ref "R50") (pin "1") (pinfunction "1_1") (pintype "passive"))
      (node (ref "RN4") (pin "1") (pinfunction "1_1") (pintype "passive"))
    )
    (net (code "15") (name "LED2") (class "Default")
      (node (ref "IC1") (pin "10") (pinfunction "PD6(AIN0)_10") (pintype "bidirectional"))
      (node (ref "RN1") (pin "8") (pinfunction "8_8") (pintype "passive"))
      (node (ref "RN4") (pin "8") (pinfunction "8_8") (pintype "passive"))
      (node (ref "X3") (pin "4") (pinfunction "S_4") (pintype "passive"))
    )
    (net (code "16") (name "LEDL") (class "Default")
      (node (ref "R21") (pin "1") (pinfunction "1_1") (pintype "passive"))
      (node (ref "R22") (pin "1") (pinfunction "1_1") (pintype "passive"))
      (node (ref "X1") (pin "3") (pinfunction "S_3") (pintype "passive"))
    )
    (net (code "17") (name "LED_OUT") (class "Default")
      (node (ref "J10") (pin "2") (pinfunction "2_2") (pintype "passive"))
      (node (ref "J3") (pin "2") (pinfunction "2_2") (pintype "passive"))
      (node (ref "J4") (pin "2") (pinfunction "2_2") (pintype "passive"))
      (node (ref "J7") (pin "2") (pinfunction "2_2") (pintype "passive"))
      (node (ref "JP5") (pin "2") (pinfunction "2_2") (pintype "passive"))
      (node (ref "LED15") (pin "3") (pinfunction "DO_3") (pintype "output"))
      (node (ref "LED17") (pin "3") (pinfunction "DO_3") (pintype "output"))
      (node (ref "LED45") (pin "3") (pinfunction "DO_3") (pintype "output"))
      (node (ref "R2") (pin "2") (pinfunction "2_2") (pintype "passive"))
      (node (ref "R22") (pin "2") (pinfunction "2_2") (pintype "passive"))
      (node (ref "R31") (pin "2") (pinfunction "2_2") (pintype "passive"))
      (node (ref "R49") (pin "2") (pinfunction "2_2") (pintype "passive"))
      (node (ref "RN1") (pin "1") (pinfunction "1_1") (pintype "passive"))
    )
    (net (code "18") (name "MISO") (class "Default")
      (node (ref "IC1") (pin "16") (pinfunction "PB4(MISO)_16") (pintype "bidirectional"))
      (node (ref "R19") (pin "1") (pinfunction "1_1") (pintype "passive"))
      (node (ref "SL1") (pin "3") (pinfunction "3_3") (pintype "passive"))
      (node (ref "SL2") (pin "2") (pinfunction "2_2") (pintype "passive"))
      (node (ref "U$1") (pin "3") (pinfunction "3_3") (pintype "passive"))
      (node (ref "X2") (pin "5") (pinfunction "S_5") (pintype "passive"))
      (node (ref "X4") (pin "3") (pinfunction "MISO_3") (pintype "bidirectional"))
      (node (ref "X5") (pin "2") (pinfunction "S_2") (pintype "passive"))
    )
    (net (code "19") (name "MOSI") (class "Default")
      (node (ref "IC1") (pin "15") (pinfunction "PB3(MOSI/OC2)_15") (pintype "bidirectional"))
      (node (ref "R18") (pin "1") (pinfunction "1_1") (pintype "passive"))
      (node (ref "SL1") (pin "2") (pinfunction "2_2") (pintype "passive"))
      (node (ref "SL2") (pin "3") (pinfunction "3_3") (pintype "passive"))
      (node (ref "U$1") (pin "2") (pinfunction "2_2") (pintype "passive"))
      (node (ref "X2") (pin "4") (pinfunction "S_4") (pintype "passive"))
      (node (ref "X4") (pin "2") (pinfunction "MOSI_2") (pintype "bidirectional"))
      (node (ref "X5") (pin "3") (pinfunction "S_3") (pintype "passive"))
    )
    (net (code "20") (name "Net-(D1-Pad+)") (class "Default")
      (node (ref "D1") (pin "+") (pinfunction "+_+") (pintype "passive"))
      (node (ref "R40") (pin "2") (pinfunction "2_2") (pintype "passive"))
    )
    (net (code "21") (name "Net-(IC1-AREF)") (class "Default")
      (node (ref "C25") (pin "1") (pinfunction "1_1") (pintype "passive"))
      (node (ref "IC1") (pin "20") (pinfunction "AREF_20") (pintype "passive"))
    )
    (net (code "22") (name "Net-(IC2-SNS)") (class "Default")
      (node (ref "C16") (pin "2") (pinfunction "2_2") (pintype "passive"))
      (node (ref "IC2") (pin "4") (pinfunction "SNS_4") (pintype "bidirectional"))
    )
    (net (code "23") (name "Net-(IC2-SNSK)") (class "Default")
      (node (ref "C16") (pin "1") (pinfunction "1_1") (pintype "passive"))
      (node (ref "IC2") (pin "3") (pinfunction "SNSK_3") (pintype "bidirectional"))
      (node (ref "R16") (pin "2") (pinfunction "2_2") (pintype "passive"))
    )
    (net (code "24") (name "Net-(LED1-DO)") (class "Default")
      (node (ref "LED1") (pin "3") (pinfunction "DO_3") (pintype "output"))
      (node (ref "LED2") (pin "1") (pinfunction "DI_1") (pintype "input"))
      (node (ref "R3") (pin "2") (pinfunction "2_2") (pintype "passive"))
      (node (ref "R4") (pin "1") (pinfunction "1_1") (pintype "passive"))
    )
    (net (code "25") (name "Net-(LED2-DO)") (class "Default")
      (node (ref "LED2") (pin "3") (pinfunction "DO_3") (pintype "output"))
      (node (ref "LED3") (pin "1") (pinfunction "DI_1") (pintype "input"))
      (node (ref "R4") (pin "2") (pinfunction "2_2") (pintype "passive"))
      (node (ref "R5") (pin "1") (pinfunction "1_1") (pintype "passive"))
    )
    (net (code "26") (name "Net-(LED3-DO)") (class "Default")
      (node (ref "LED3") (pin "3") (pinfunction "DO_3") (pintype "output"))
      (node (ref "LED4") (pin "1") (pinfunction "DI_1") (pintype "input"))
      (node (ref "R5") (pin "2") (pinfunction "2_2") (pintype "passive"))
      (node (ref "R6") (pin "1") (pinfunction "1_1") (pintype "passive"))
    )
    (net (code "27") (name "Net-(LED4-DO)") (class "Default")
      (node (ref "LED4") (pin "3") (pinfunction "DO_3") (pintype "output"))
      (node (ref "LED5") (pin "1") (pinfunction "DI_1") (pintype "input"))
      (node (ref "R6") (pin "2") (pinfunction "2_2") (pintype "passive"))
      (node (ref "R7") (pin "1") (pinfunction "1_1") (pintype "passive"))
    )
    (net (code "28") (name "Net-(LED5-DO)") (class "Default")
      (node (ref "LED5") (pin "3") (pinfunction "DO_3") (pintype "output"))
      (node (ref "LED6") (pin "1") (pinfunction "DI_1") (pintype "input"))
      (node (ref "R7") (pin "2") (pinfunction "2_2") (pintype "passive"))
      (node (ref "R8") (pin "1") (pinfunction "1_1") (pintype "passive"))
    )
    (net (code "29") (name "Net-(LED6-DO)") (class "Default")
      (node (ref "LED6") (pin "3") (pinfunction "DO_3") (pintype "output"))
      (node (ref "LED7") (pin "1") (pinfunction "DI_1") (pintype "input"))
      (node (ref "R8") (pin "2") (pinfunction "2_2") (pintype "passive"))
      (node (ref "R9") (pin "1") (pinfunction "1_1") (pintype "passive"))
    )
    (net (code "30") (name "Net-(LED7-DO)") (class "Default")
      (node (ref "LED7") (pin "3") (pinfunction "DO_3") (pintype "output"))
      (node (ref "LED8") (pin "1") (pinfunction "DI_1") (pintype "input"))
      (node (ref "R10") (pin "1") (pinfunction "1_1") (pintype "passive"))
      (node (ref "R9") (pin "2") (pinfunction "2_2") (pintype "passive"))
    )
    (net (code "31") (name "Net-(LED8-DO)") (class "Default")
      (node (ref "LED8") (pin "3") (pinfunction "DO_3") (pintype "output"))
      (node (ref "LED9") (pin "1") (pinfunction "DI_1") (pintype "input"))
      (node (ref "R10") (pin "2") (pinfunction "2_2") (pintype "passive"))
      (node (ref "R11") (pin "1") (pinfunction "1_1") (pintype "passive"))
    )
    (net (code "32") (name "Net-(LED10-DI)") (class "Default")
      (node (ref "LED10") (pin "1") (pinfunction "DI_1") (pintype "input"))
      (node (ref "LED9") (pin "3") (pinfunction "DO_3") (pintype "output"))
      (node (ref "R11") (pin "2") (pinfunction "2_2") (pintype "passive"))
      (node (ref "R12") (pin "1") (pinfunction "1_1") (pintype "passive"))
    )
    (net (code "33") (name "Net-(LED10-DO)") (class "Default")
      (node (ref "LED10") (pin "3") (pinfunction "DO_3") (pintype "output"))
      (node (ref "LED11") (pin "1") (pinfunction "DI_1") (pintype "input"))
      (node (ref "R12") (pin "2") (pinfunction "2_2") (pintype "passive"))
      (node (ref "R13") (pin "1") (pinfunction "1_1") (pintype "passive"))
    )
    (net (code "34") (name "Net-(LED11-DO)") (class "Default")
      (node (ref "LED11") (pin "3") (pinfunction "DO_3") (pintype "output"))
      (node (ref "LED12") (pin "1") (pinfunction "DI_1") (pintype "input"))
      (node (ref "R13") (pin "2") (pinfunction "2_2") (pintype "passive"))
      (node (ref "R14") (pin "1") (pinfunction "1_1") (pintype "passive"))
    )
    (net (code "35") (name "Net-(LED12-DO)") (class "Default")
      (node (ref "LED12") (pin "3") (pinfunction "DO_3") (pintype "output"))
      (node (ref "LED13") (pin "1") (pinfunction "DI_1") (pintype "input"))
      (node (ref "R14") (pin "2") (pinfunction "2_2") (pintype "passive"))
      (node (ref "R15") (pin "1") (pinfunction "1_1") (pintype "passive"))
    )
    (net (code "36") (name "Net-(LED13-DO)") (class "Default")
      (node (ref "LED13") (pin "3") (pinfunction "DO_3") (pintype "output"))
      (node (ref "LED14") (pin "1") (pinfunction "DI_1") (pintype "input"))
      (node (ref "R1") (pin "1") (pinfunction "1_1") (pintype "passive"))
      (node (ref "R15") (pin "2") (pinfunction "2_2") (pintype "passive"))
    )
    (net (code "37") (name "Net-(LED14-DO)") (class "Default")
      (node (ref "LED14") (pin "3") (pinfunction "DO_3") (pintype "output"))
      (node (ref "LED15") (pin "1") (pinfunction "DI_1") (pintype "input"))
      (node (ref "R1") (pin "2") (pinfunction "2_2") (pintype "passive"))
      (node (ref "R2") (pin "1") (pinfunction "1_1") (pintype "passive"))
    )
    (net (code "38") (name "Net-(LED16-DO)") (class "Default")
      (node (ref "LED16") (pin "3") (pinfunction "DO_3") (pintype "output"))
      (node (ref "LED18") (pin "1") (pinfunction "DI_1") (pintype "input"))
      (node (ref "R26") (pin "1") (pinfunction "1_1") (pintype "passive"))
      (node (ref "R30") (pin "1") (pinfunction "1_1") (pintype "passive"))
    )
    (net (code "39") (name "Net-(LED17-DI)") (class "Default")
      (node (ref "LED17") (pin "1") (pinfunction "DI_1") (pintype "input"))
      (node (ref "LED19") (pin "3") (pinfunction "DO_3") (pintype "output"))
      (node (ref "R29") (pin "2") (pinfunction "2_2") (pintype "passive"))
      (node (ref "R31") (pin "1") (pinfunction "1_1") (pintype "passive"))
    )
    (net (code "40") (name "Net-(LED18-DO)") (class "Default")
      (node (ref "LED18") (pin "3") (pinfunction "DO_3") (pintype "output"))
      (node (ref "LED19") (pin "1") (pinfunction "DI_1") (pintype "input"))
      (node (ref "R26") (pin "2") (pinfunction "2_2") (pintype "passive"))
      (node (ref "R29") (pin "1") (pinfunction "1_1") (pintype "passive"))
    )
    (net (code "41") (name "Net-(LED31-DO)") (class "Default")
      (node (ref "LED31") (pin "3") (pinfunction "DO_3") (pintype "output"))
      (node (ref "LED32") (pin "1") (pinfunction "DI_1") (pintype "input"))
      (node (ref "R50") (pin "2") (pinfunction "2_2") (pintype "passive"))
      (node (ref "R51") (pin "1") (pinfunction "1_1") (pintype "passive"))
    )
    (net (code "42") (name "Net-(LED32-DO)") (class "Default")
      (node (ref "LED32") (pin "3") (pinfunction "DO_3") (pintype "output"))
      (node (ref "LED33") (pin "1") (pinfunction "DI_1") (pintype "input"))
      (node (ref "R51") (pin "2") (pinfunction "2_2") (pintype "passive"))
      (node (ref "R52") (pin "1") (pinfunction "1_1") (pintype "passive"))
    )
    (net (code "43") (name "Net-(LED33-DO)") (class "Default")
      (node (ref "LED33") (pin "3") (pinfunction "DO_3") (pintype "output"))
      (node (ref "LED34") (pin "1") (pinfunction "DI_1") (pintype "input"))
      (node (ref "R52") (pin "2") (pinfunction "2_2") (pintype "passive"))
      (node (ref "R53") (pin "1") (pinfunction "1_1") (pintype "passive"))
    )
    (net (code "44") (name "Net-(LED34-DO)") (class "Default")
      (node (ref "LED34") (pin "3") (pinfunction "DO_3") (pintype "output"))
      (node (ref "LED35") (pin "1") (pinfunction "DI_1") (pintype "input"))
      (node (ref "R53") (pin "2") (pinfunction "2_2") (pintype "passive"))
      (node (ref "R54") (pin "1") (pinfunction "1_1") (pintype "passive"))
    )
    (net (code "45") (name "Net-(LED35-DO)") (class "Default")
      (node (ref "LED35") (pin "3") (pinfunction "DO_3") (pintype "output"))
      (node (ref "LED36") (pin "1") (pinfunction "DI_1") (pintype "input"))
      (node (ref "R54") (pin "2") (pinfunction "2_2") (pintype "passive"))
      (node (ref "R55") (pin "1") (pinfunction "1_1") (pintype "passive"))
    )
    (net (code "46") (name "Net-(LED36-DO)") (class "Default")
      (node (ref "LED36") (pin "3") (pinfunction "DO_3") (pintype "output"))
      (node (ref "LED37") (pin "1") (pinfunction "DI_1") (pintype "input"))
      (node (ref "R41") (pin "1") (pinfunction "1_1") (pintype "passive"))
      (node (ref "R55") (pin "2") (pinfunction "2_2") (pintype "passive"))
    )
    (net (code "47") (name "Net-(LED37-DO)") (class "Default")
      (node (ref "LED37") (pin "3") (pinfunction "DO_3") (pintype "output"))
      (node (ref "LED38") (pin "1") (pinfunction "DI_1") (pintype "input"))
      (node (ref "R41") (pin "2") (pinfunction "2_2") (pintype "passive"))
      (node (ref "R42") (pin "1") (pinfunction "1_1") (pintype "passive"))
    )
    (net (code "48") (name "Net-(LED38-DO)") (class "Default")
      (node (ref "LED38") (pin "3") (pinfunction "DO_3") (pintype "output"))
      (node (ref "LED39") (pin "1") (pinfunction "DI_1") (pintype "input"))
      (node (ref "R42") (pin "2") (pinfunction "2_2") (pintype "passive"))
      (node (ref "R43") (pin "1") (pinfunction "1_1") (pintype "passive"))
    )
    (net (code "49") (name "Net-(LED39-DO)") (class "Default")
      (node (ref "LED39") (pin "3") (pinfunction "DO_3") (pintype "output"))
      (node (ref "LED40") (pin "1") (pinfunction "DI_1") (pintype "input"))
      (node (ref "R43") (pin "2") (pinfunction "2_2") (pintype "passive"))
      (node (ref "R44") (pin "1") (pinfunction "1_1") (pintype "passive"))
    )
    (net (code "50") (name "Net-(LED40-DO)") (class "Default")
      (node (ref "LED40") (pin "3") (pinfunction "DO_3") (pintype "output"))
      (node (ref "LED41") (pin "1") (pinfunction "DI_1") (pintype "input"))
      (node (ref "R44") (pin "2") (pinfunction "2_2") (pintype "passive"))
      (node (ref "R45") (pin "1") (pinfunction "1_1") (pintype "passive"))
    )
    (net (code "51") (name "Net-(LED41-DO)") (class "Default")
      (node (ref "LED41") (pin "3") (pinfunction "DO_3") (pintype "output"))
      (node (ref "LED42") (pin "1") (pinfunction "DI_1") (pintype "input"))
      (node (ref "R45") (pin "2") (pinfunction "2_2") (pintype "passive"))
      (node (ref "R46") (pin "1") (pinfunction "1_1") (pintype "passive"))
    )
    (net (code "52") (name "Net-(LED42-DO)") (class "Default")
      (node (ref "LED42") (pin "3") (pinfunction "DO_3") (pintype "output"))
      (node (ref "LED43") (pin "1") (pinfunction "DI_1") (pintype "input"))
      (node (ref "R46") (pin "2") (pinfunction "2_2") (pintype "passive"))
      (node (ref "R47") (pin "1") (pinfunction "1_1") (pintype "passive"))
    )
    (net (code "53") (name "Net-(LED43-DO)") (class "Default")
      (node (ref "LED43") (pin "3") (pinfunction "DO_3") (pintype "output"))
      (node (ref "LED44") (pin "1") (pinfunction "DI_1") (pintype "input"))
      (node (ref "R47") (pin "2") (pinfunction "2_2") (pintype "passive"))
      (node (ref "R48") (pin "1") (pinfunction "1_1") (pintype "passive"))
    )
    (net (code "54") (name "Net-(LED44-DO)") (class "Default")
      (node (ref "LED44") (pin "3") (pinfunction "DO_3") (pintype "output"))
      (node (ref "LED45") (pin "1") (pinfunction "DI_1") (pintype "input"))
      (node (ref "R48") (pin "2") (pinfunction "2_2") (pintype "passive"))
      (node (ref "R49") (pin "1") (pinfunction "1_1") (pintype "passive"))
    )
    (net (code "55") (name "PAD") (class "Default")
      (node (ref "R16") (pin "1") (pinfunction "1_1") (pintype "passive"))
    )
    (net (code "56") (name "POT") (class "Default")
      (node (ref "JP1") (pin "2") (pinfunction "2_2") (pintype "passive"))
      (node (ref "R25") (pin "2") (pinfunction "S_2") (pintype "passive"))
      (node (ref "R27") (pin "1") (pinfunction "1_1") (pintype "passive"))
      (node (ref "R34") (pin "1") (pinfunction "1_1") (pintype "passive"))
      (node (ref "R36") (pin "2") (pinfunction "2_2") (pintype "passive"))
      (node (ref "R37") (pin "2") (pinfunction "2_2") (pintype "passive"))
      (node (ref "S1") (pin "SIG1") (pinfunction "SIG1_SIG1") (pintype "bidirectional"))
    )
    (net (code "57") (name "POT+") (class "Default")
      (node (ref "R23") (pin "1") (pinfunction "1_1") (pintype "passive"))
      (node (ref "R25") (pin "1") (pinfunction "A_1") (pintype "passive"))
    )
    (net (code "58") (name "RST") (class "Default")
      (node (ref "SL1") (pin "1") (pinfunction "1_1") (pintype "passive"))
      (node (ref "U$1") (pin "1") (pinfunction "1_1") (pintype "passive"))
    )
    (net (code "59") (name "RXD") (class "Default")
      (node (ref "CN1") (pin "4") (pinfunction "4_4") (pintype "bidirectional"))
      (node (ref "SH1") (pin "P$2") (pinfunction "P$2_P$2") (pintype "bidirectional"))
    )
    (net (code "60") (name "SCK") (class "Default")
      (node (ref "IC1") (pin "17") (pinfunction "PB5(SCK)_17") (pintype "bidirectional"))
      (node (ref "R20") (pin "1") (pinfunction "1_1") (pintype "passive"))
      (node (ref "SL1") (pin "4") (pinfunction "4_4") (pintype "passive"))
      (node (ref "SL2") (pin "1") (pinfunction "1_1") (pintype "passive"))
      (node (ref "U$1") (pin "4") (pinfunction "4_4") (pintype "passive"))
      (node (ref "X2") (pin "6") (pinfunction "S_6") (pintype "passive"))
      (node (ref "X4") (pin "4") (pinfunction "SCK_4") (pintype "bidirectional"))
      (node (ref "X5") (pin "1") (pinfunction "S_1") (pintype "passive"))
    )
    (net (code "61") (name "SCL") (class "Default")
      (node (ref "IC1") (pin "28") (pinfunction "PC5(ADC5/SCL)_28") (pintype "bidirectional"))
      (node (ref "SL2") (pin "5") (pinfunction "5_5") (pintype "passive"))
      (node (ref "X2") (pin "2") (pinfunction "S_2") (pintype "passive"))
      (node (ref "X5") (pin "5") (pinfunction "S_5") (pintype "passive"))
    )
    (net (code "62") (name "SDA") (class "Default")
      (node (ref "IC1") (pin "27") (pinfunction "PC4(ADC4/SDA)_27") (pintype "bidirectional"))
      (node (ref "SL2") (pin "6") (pinfunction "6_6") (pintype "passive"))
      (node (ref "X2") (pin "1") (pinfunction "S_1") (pintype "passive"))
      (node (ref "X5") (pin "6") (pinfunction "S_6") (pintype "passive"))
    )
    (net (code "63") (name "SW1") (class "Default")
      (node (ref "IC1") (pin "23") (pinfunction "PC0(ADC0)_23") (pintype "bidirectional"))
      (node (ref "R24") (pin "2") (pinfunction "2_2") (pintype "passive"))
      (node (ref "R27") (pin "2") (pinfunction "2_2") (pintype "passive"))
      (node (ref "R28") (pin "2") (pinfunction "2_2") (pintype "passive"))
      (node (ref "RN2") (pin "5") (pinfunction "5_5") (pintype "passive"))
      (node (ref "RN3") (pin "7") (pinfunction "7_7") (pintype "passive"))
    )
    (net (code "64") (name "SWL") (class "Default")
      (node (ref "IC1") (pin "24") (pinfunction "PC1(ADC1)_24") (pintype "bidirectional"))
      (node (ref "RN2") (pin "6") (pinfunction "6_6") (pintype "passive"))
      (node (ref "RN3") (pin "8") (pinfunction "8_8") (pintype "passive"))
      (node (ref "X1") (pin "6") (pinfunction "S_6") (pintype "passive"))
    )
    (net (code "65") (name "SWR") (class "Default")
      (node (ref "IC1") (pin "25") (pinfunction "PC2(ADC2)_25") (pintype "bidirectional"))
      (node (ref "RN2") (pin "3") (pinfunction "3_3") (pintype "passive"))
      (node (ref "RN2") (pin "4") (pinfunction "4_4") (pintype "passive"))
      (node (ref "RN3") (pin "1") (pinfunction "1_1") (pintype "passive"))
      (node (ref "RN3") (pin "2") (pinfunction "2_2") (pintype "passive"))
      (node (ref "X3") (pin "1") (pinfunction "S_1") (pintype "passive"))
    )
    (net (code "66") (name "TOUCH") (class "Default")
      (node (ref "IC1") (pin "11") (pinfunction "PD7(AIN1)_11") (pintype "bidirectional"))
      (node (ref "IC2") (pin "1") (pinfunction "OUT_1") (pintype "bidirectional"))
      (node (ref "R24") (pin "1") (pinfunction "1_1") (pintype "passive"))
      (node (ref "R38") (pin "2") (pinfunction "2_2") (pintype "passive"))
      (node (ref "R39") (pin "2") (pinfunction "2_2") (pintype "passive"))
    )
    (net (code "67") (name "TXD") (class "Default")
      (node (ref "CN1") (pin "5") (pinfunction "5_5") (pintype "bidirectional"))
      (node (ref "SH2") (pin "P$2") (pinfunction "P$2_P$2") (pintype "bidirectional"))
    )
    (net (code "68") (name "VCC") (class "Default")
      (node (ref "C1") (pin "1") (pinfunction "1_1") (pintype "passive"))
      (node (ref "C10") (pin "1") (pinfunction "1_1") (pintype "passive"))
      (node (ref "C11") (pin "1") (pinfunction "1_1") (pintype "passive"))
      (node (ref "C12") (pin "1") (pinfunction "1_1") (pintype "passive"))
      (node (ref "C13") (pin "1") (pinfunction "1_1") (pintype "passive"))
      (node (ref "C14") (pin "1") (pinfunction "1_1") (pintype "passive"))
      (node (ref "C15") (pin "1") (pinfunction "1_1") (pintype "passive"))
      (node (ref "C17") (pin "1") (pinfunction "1_1") (pintype "passive"))
      (node (ref "C19") (pin "+") (pinfunction "+_+") (pintype "passive"))
      (node (ref "C2") (pin "1") (pinfunction "1_1") (pintype "passive"))
      (node (ref "C20") (pin "1") (pinfunction "1_1") (pintype "passive"))
      (node (ref "C21") (pin "1") (pinfunction "1_1") (pintype "passive"))
      (node (ref "C22") (pin "1") (pinfunction "1_1") (pintype "passive"))
      (node (ref "C23") (pin "1") (pinfunction "1_1") (pintype "passive"))
      (node (ref "C24") (pin "1") (pinfunction "1_1") (pintype "passive"))
      (node (ref "C26") (pin "1") (pinfunction "1_1") (pintype "passive"))
      (node (ref "C3") (pin "1") (pinfunction "1_1") (pintype "passive"))
      (node (ref "C4") (pin "1") (pinfunction "1_1") (pintype "passive"))
      (node (ref "C41") (pin "1") (pinfunction "1_1") (pintype "passive"))
      (node (ref "C42") (pin "1") (pinfunction "1_1") (pintype "passive"))
      (node (ref "C43") (pin "1") (pinfunction "1_1") (pintype "passive"))
      (node (ref "C44") (pin "1") (pinfunction "1_1") (pintype "passive"))
      (node (ref "C45") (pin "1") (pinfunction "1_1") (pintype "passive"))
      (node (ref "C46") (pin "1") (pinfunction "1_1") (pintype "passive"))
      (node (ref "C47") (pin "1") (pinfunction "1_1") (pintype "passive"))
      (node (ref "C48") (pin "1") (pinfunction "1_1") (pintype "passive"))
      (node (ref "C49") (pin "1") (pinfunction "1_1") (pintype "passive"))
      (node (ref "C5") (pin "1") (pinfunction "1_1") (pintype "passive"))
      (node (ref "C50") (pin "1") (pinfunction "1_1") (pintype "passive"))
      (node (ref "C51") (pin "1") (pinfunction "1_1") (pintype "passive"))
      (node (ref "C52") (pin "1") (pinfunction "1_1") (pintype "passive"))
      (node (ref "C53") (pin "1") (pinfunction "1_1") (pintype "passive"))
      (node (ref "C54") (pin "1") (pinfunction "1_1") (pintype "passive"))
      (node (ref "C55") (pin "1") (pinfunction "1_1") (pintype "passive"))
      (node (ref "C6") (pin "1") (pinfunction "1_1") (pintype "passive"))
      (node (ref "C7") (pin "1") (pinfunction "1_1") (pintype "passive"))
      (node (ref "C8") (pin "1") (pinfunction "1_1") (pintype "passive"))
      (node (ref "C9") (pin "1") (pinfunction "1_1") (pintype "passive"))
      (node (ref "CN1") (pin "3") (pinfunction "3_3") (pintype "bidirectional"))
      (node (ref "IC1") (pin "18") (pinfunction "AVCC_18") (pintype "power_in"))
      (node (ref "IC1") (pin "4") (pinfunction "VCC_4") (pintype "power_in"))
      (node (ref "IC1") (pin "6") (pinfunction "VCC_6") (pintype "power_in"))
      (node (ref "IC2") (pin "5") (pinfunction "VDD_5") (pintype "bidirectional"))
      (node (ref "J1") (pin "1") (pinfunction "1_1") (pintype "passive"))
      (node (ref "J10") (pin "1") (pinfunction "1_1") (pintype "passive"))
      (node (ref "J11") (pin "1") (pinfunction "1_1") (pintype "passive"))
      (node (ref "J12") (pin "1") (pinfunction "1_1") (pintype "passive"))
      (node (ref "J13") (pin "1") (pinfunction "1_1") (pintype "passive"))
      (node (ref "J14") (pin "1") (pinfunction "1_1") (pintype "passive"))
      (node (ref "J2") (pin "1") (pinfunction "1_1") (pintype "passive"))
      (node (ref "J3") (pin "1") (pinfunction "1_1") (pintype "passive"))
      (node (ref "J4") (pin "1") (pinfunction "1_1") (pintype "passive"))
      (node (ref "J5") (pin "1") (pinfunction "1_1") (pintype "passive"))
      (node (ref "J6") (pin "1") (pinfunction "1_1") (pintype "passive"))
      (node (ref "J7") (pin "1") (pinfunction "1_1") (pintype "passive"))
      (node (ref "JP5") (pin "1") (pinfunction "1_1") (pintype "passive"))
      (node (ref "LED1") (pin "2") (pinfunction "VDD_2") (pintype "power_in"))
      (node (ref "LED10") (pin "2") (pinfunction "VDD_2") (pintype "power_in"))
      (node (ref "LED11") (pin "2") (pinfunction "VDD_2") (pintype "power_in"))
      (node (ref "LED12") (pin "2") (pinfunction "VDD_2") (pintype "power_in"))
      (node (ref "LED13") (pin "2") (pinfunction "VDD_2") (pintype "power_in"))
      (node (ref "LED14") (pin "2") (pinfunction "VDD_2") (pintype "power_in"))
      (node (ref "LED15") (pin "2") (pinfunction "VDD_2") (pintype "power_in"))
      (node (ref "LED16") (pin "2") (pinfunction "VDD_2") (pintype "power_in"))
      (node (ref "LED17") (pin "2") (pinfunction "VDD_2") (pintype "power_in"))
      (node (ref "LED18") (pin "2") (pinfunction "VDD_2") (pintype "power_in"))
      (node (ref "LED19") (pin "2") (pinfunction "VDD_2") (pintype "power_in"))
      (node (ref "LED2") (pin "2") (pinfunction "VDD_2") (pintype "power_in"))
      (node (ref "LED3") (pin "2") (pinfunction "VDD_2") (pintype "power_in"))
      (node (ref "LED31") (pin "2") (pinfunction "VDD_2") (pintype "power_in"))
      (node (ref "LED32") (pin "2") (pinfunction "VDD_2") (pintype "power_in"))
      (node (ref "LED33") (pin "2") (pinfunction "VDD_2") (pintype "power_in"))
      (node (ref "LED34") (pin "2") (pinfunction "VDD_2") (pintype "power_in"))
      (node (ref "LED35") (pin "2") (pinfunction "VDD_2") (pintype "power_in"))
      (node (ref "LED36") (pin "2") (pinfunction "VDD_2") (pintype "power_in"))
      (node (ref "LED37") (pin "2") (pinfunction "VDD_2") (pintype "power_in"))
      (node (ref "LED38") (pin "2") (pinfunction "VDD_2") (pintype "power_in"))
      (node (ref "LED39") (pin "2") (pinfunction "VDD_2") (pintype "power_in"))
      (node (ref "LED4") (pin "2") (pinfunction "VDD_2") (pintype "power_in"))
      (node (ref "LED40") (pin "2") (pinfunction "VDD_2") (pintype "power_in"))
      (node (ref "LED41") (pin "2") (pinfunction "VDD_2") (pintype "power_in"))
      (node (ref "LED42") (pin "2") (pinfunction "VDD_2") (pintype "power_in"))
      (node (ref "LED43") (pin "2") (pinfunction "VDD_2") (pintype "power_in"))
      (node (ref "LED44") (pin "2") (pinfunction "VDD_2") (pintype "power_in"))
      (node (ref "LED45") (pin "2") (pinfunction "VDD_2") (pintype "power_in"))
      (node (ref "LED5") (pin "2") (pinfunction "VDD_2") (pintype "power_in"))
      (node (ref "LED6") (pin "2") (pinfunction "VDD_2") (pintype "power_in"))
      (node (ref "LED7") (pin "2") (pinfunction "VDD_2") (pintype "power_in"))
      (node (ref "LED8") (pin "2") (pinfunction "VDD_2") (pintype "power_in"))
      (node (ref "LED9") (pin "2") (pinfunction "VDD_2") (pintype "power_in"))
      (node (ref "POWER") (pin "9") (pinfunction "1_9") (pintype "passive"))
      (node (ref "R17") (pin "2") (pinfunction "2_2") (pintype "passive"))
      (node (ref "R23") (pin "2") (pinfunction "2_2") (pintype "passive"))
      (node (ref "R32") (pin "2") (pinfunction "2_2") (pintype "passive"))
      (node (ref "R33") (pin "2") (pinfunction "2_2") (pintype "passive"))
      (node (ref "R34") (pin "2") (pinfunction "2_2") (pintype "passive"))
      (node (ref "R35") (pin "2") (pinfunction "2_2") (pintype "passive"))
      (node (ref "SL1") (pin "6") (pinfunction "6_6") (pintype "passive"))
      (node (ref "U$1") (pin "6") (pinfunction "6_6") (pintype "passive"))
      (node (ref "X4") (pin "6") (pinfunction "VCC_6") (pintype "bidirectional"))
    )
    (net (code "69") (name "unconnected-(IC1-ADC6-Pad19)") (class "Default")
      (node (ref "IC1") (pin "19") (pinfunction "ADC6_19") (pintype "bidirectional"))
    )
    (net (code "70") (name "unconnected-(IC1-ADC7-Pad22)") (class "Default")
      (node (ref "IC1") (pin "22") (pinfunction "ADC7_22") (pintype "bidirectional"))
    )
    (net (code "71") (name "unconnected-(RN1-Pad4)") (class "Default")
      (node (ref "RN1") (pin "4") (pinfunction "4_4") (pintype "passive"))
    )
    (net (code "72") (name "unconnected-(RN1-Pad5)") (class "Default")
      (node (ref "RN1") (pin "5") (pinfunction "5_5") (pintype "passive"))
    )
    (net (code "73") (name "unconnected-(RN4-Pad4)") (class "Default")
      (node (ref "RN4") (pin "4") (pinfunction "4_4") (pintype "passive"))
    )
    (net (code "74") (name "unconnected-(RN4-Pad5)") (class "Default")
      (node (ref "RN4") (pin "5") (pinfunction "5_5") (pintype "passive"))
    )
    (net (code "75") (name "~{RESET}") (class "Default")
      (node (ref "C18") (pin "2") (pinfunction "2_2") (pintype "passive"))
      (node (ref "IC1") (pin "29") (pinfunction "PC6(/RESET)_29") (pintype "bidirectional"))
      (node (ref "R17") (pin "1") (pinfunction "1_1") (pintype "passive"))
      (node (ref "X4") (pin "1") (pinfunction "\\RST_1") (pintype "bidirectional"))
    )
    (net (code "76") (name "~{SS}") (class "Default")
      (node (ref "IC1") (pin "14") (pinfunction "PB2(SS/OC1B)_14") (pintype "bidirectional"))
      (node (ref "SL2") (pin "4") (pinfunction "4_4") (pintype "passive"))
      (node (ref "X2") (pin "3") (pinfunction "S_3") (pintype "passive"))
      (node (ref "X5") (pin "4") (pinfunction "S_4") (pintype "passive"))
    )
  )
)
